# ProProject_ads1299_stm32f407__2024-07-30.net
KiCad netlist of a schematic drawn in EasyEDA Pro
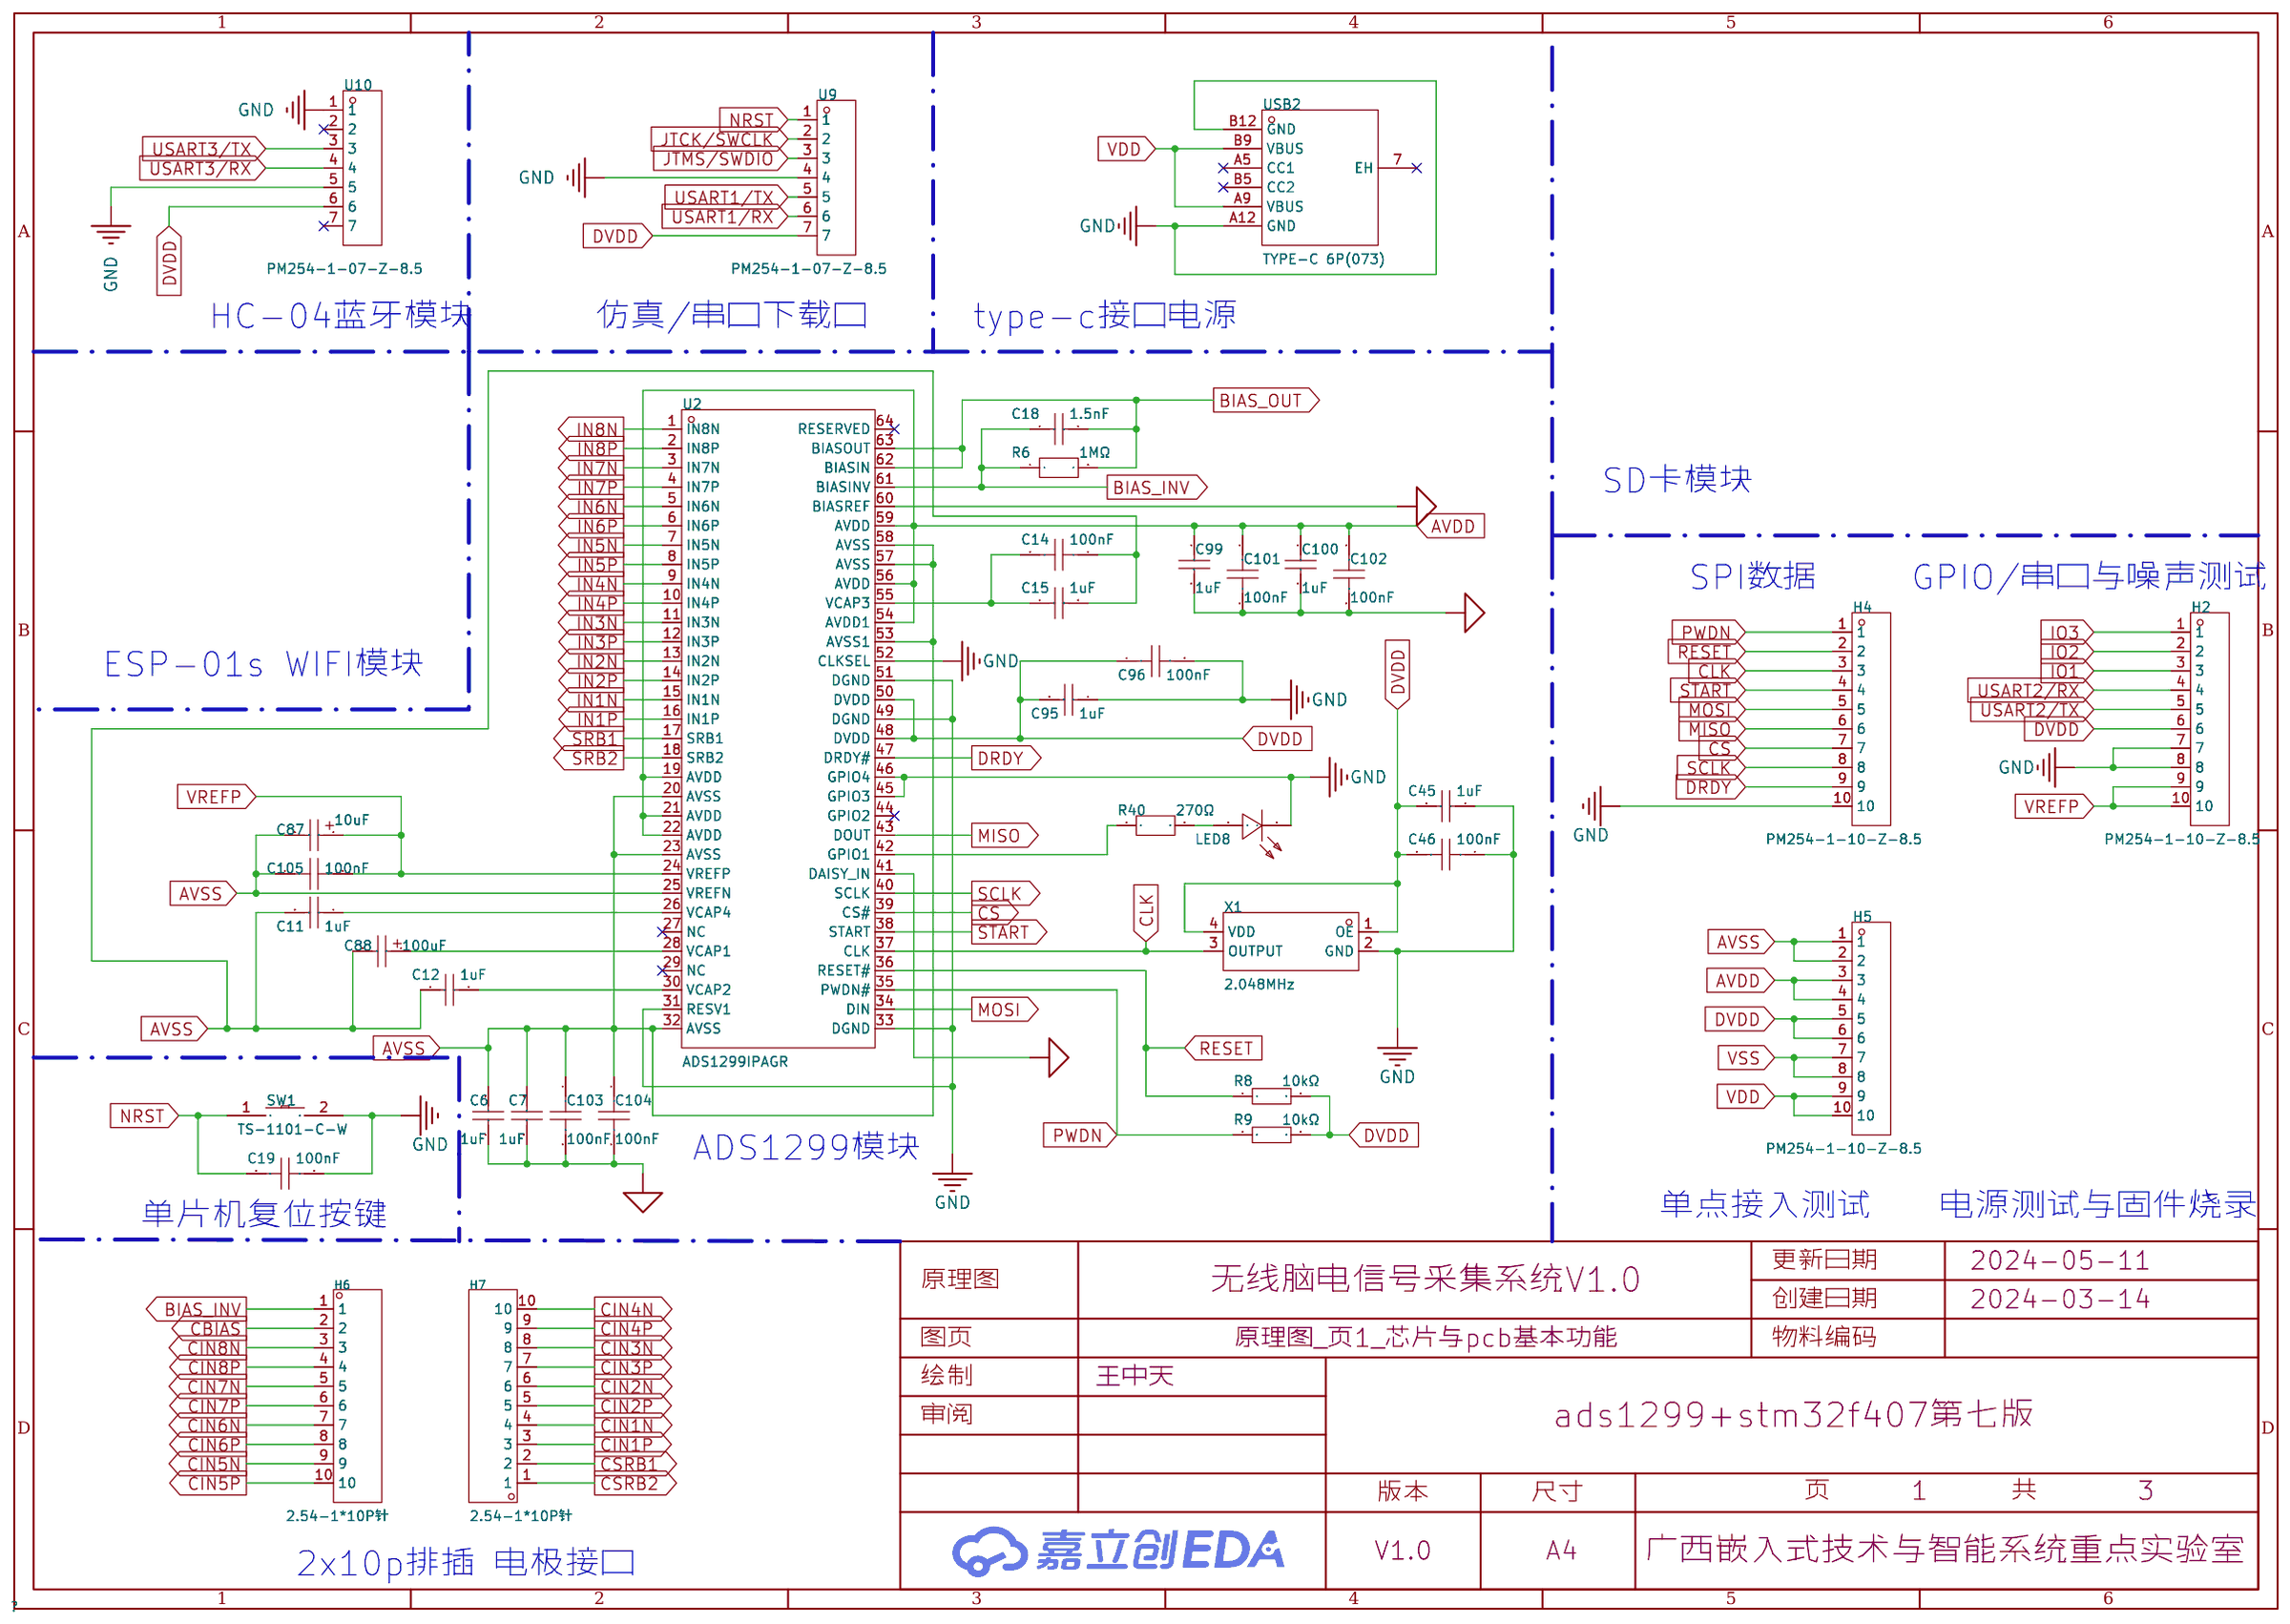
[diagram p0: 原理图_页1_芯片与pcb基本功能]
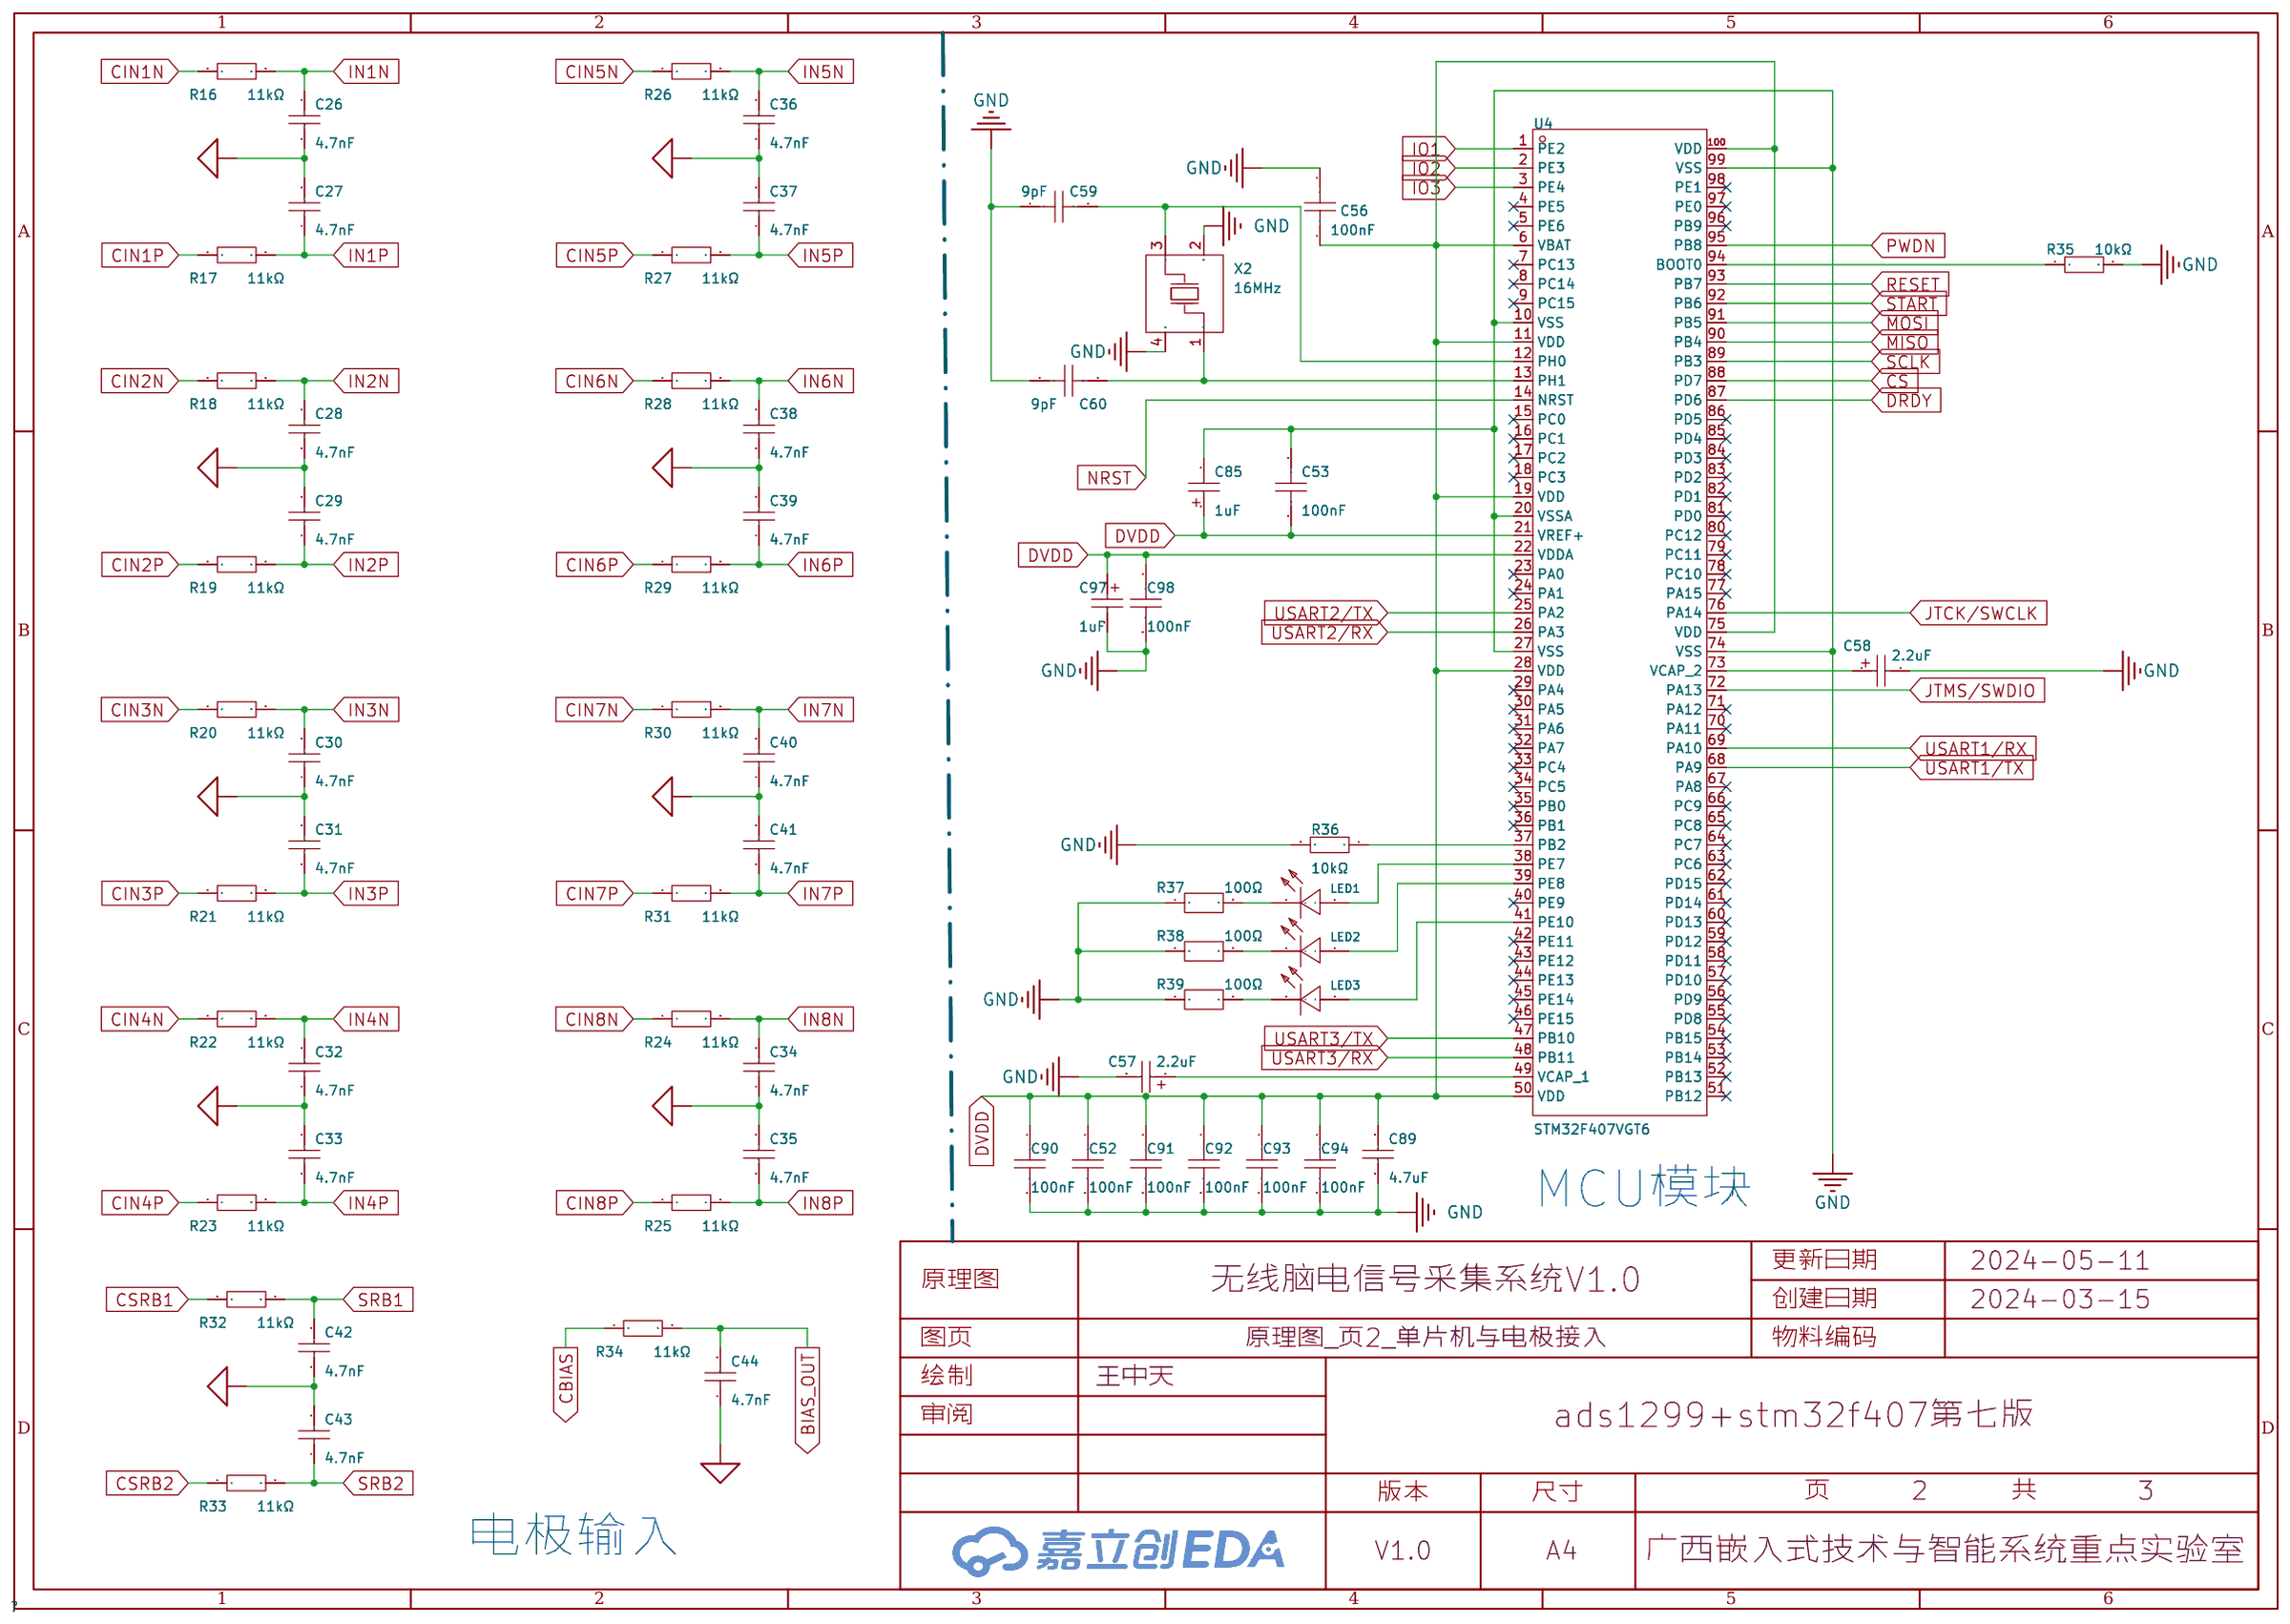
[diagram p1: 原理图_页2_单片机与电极接入]
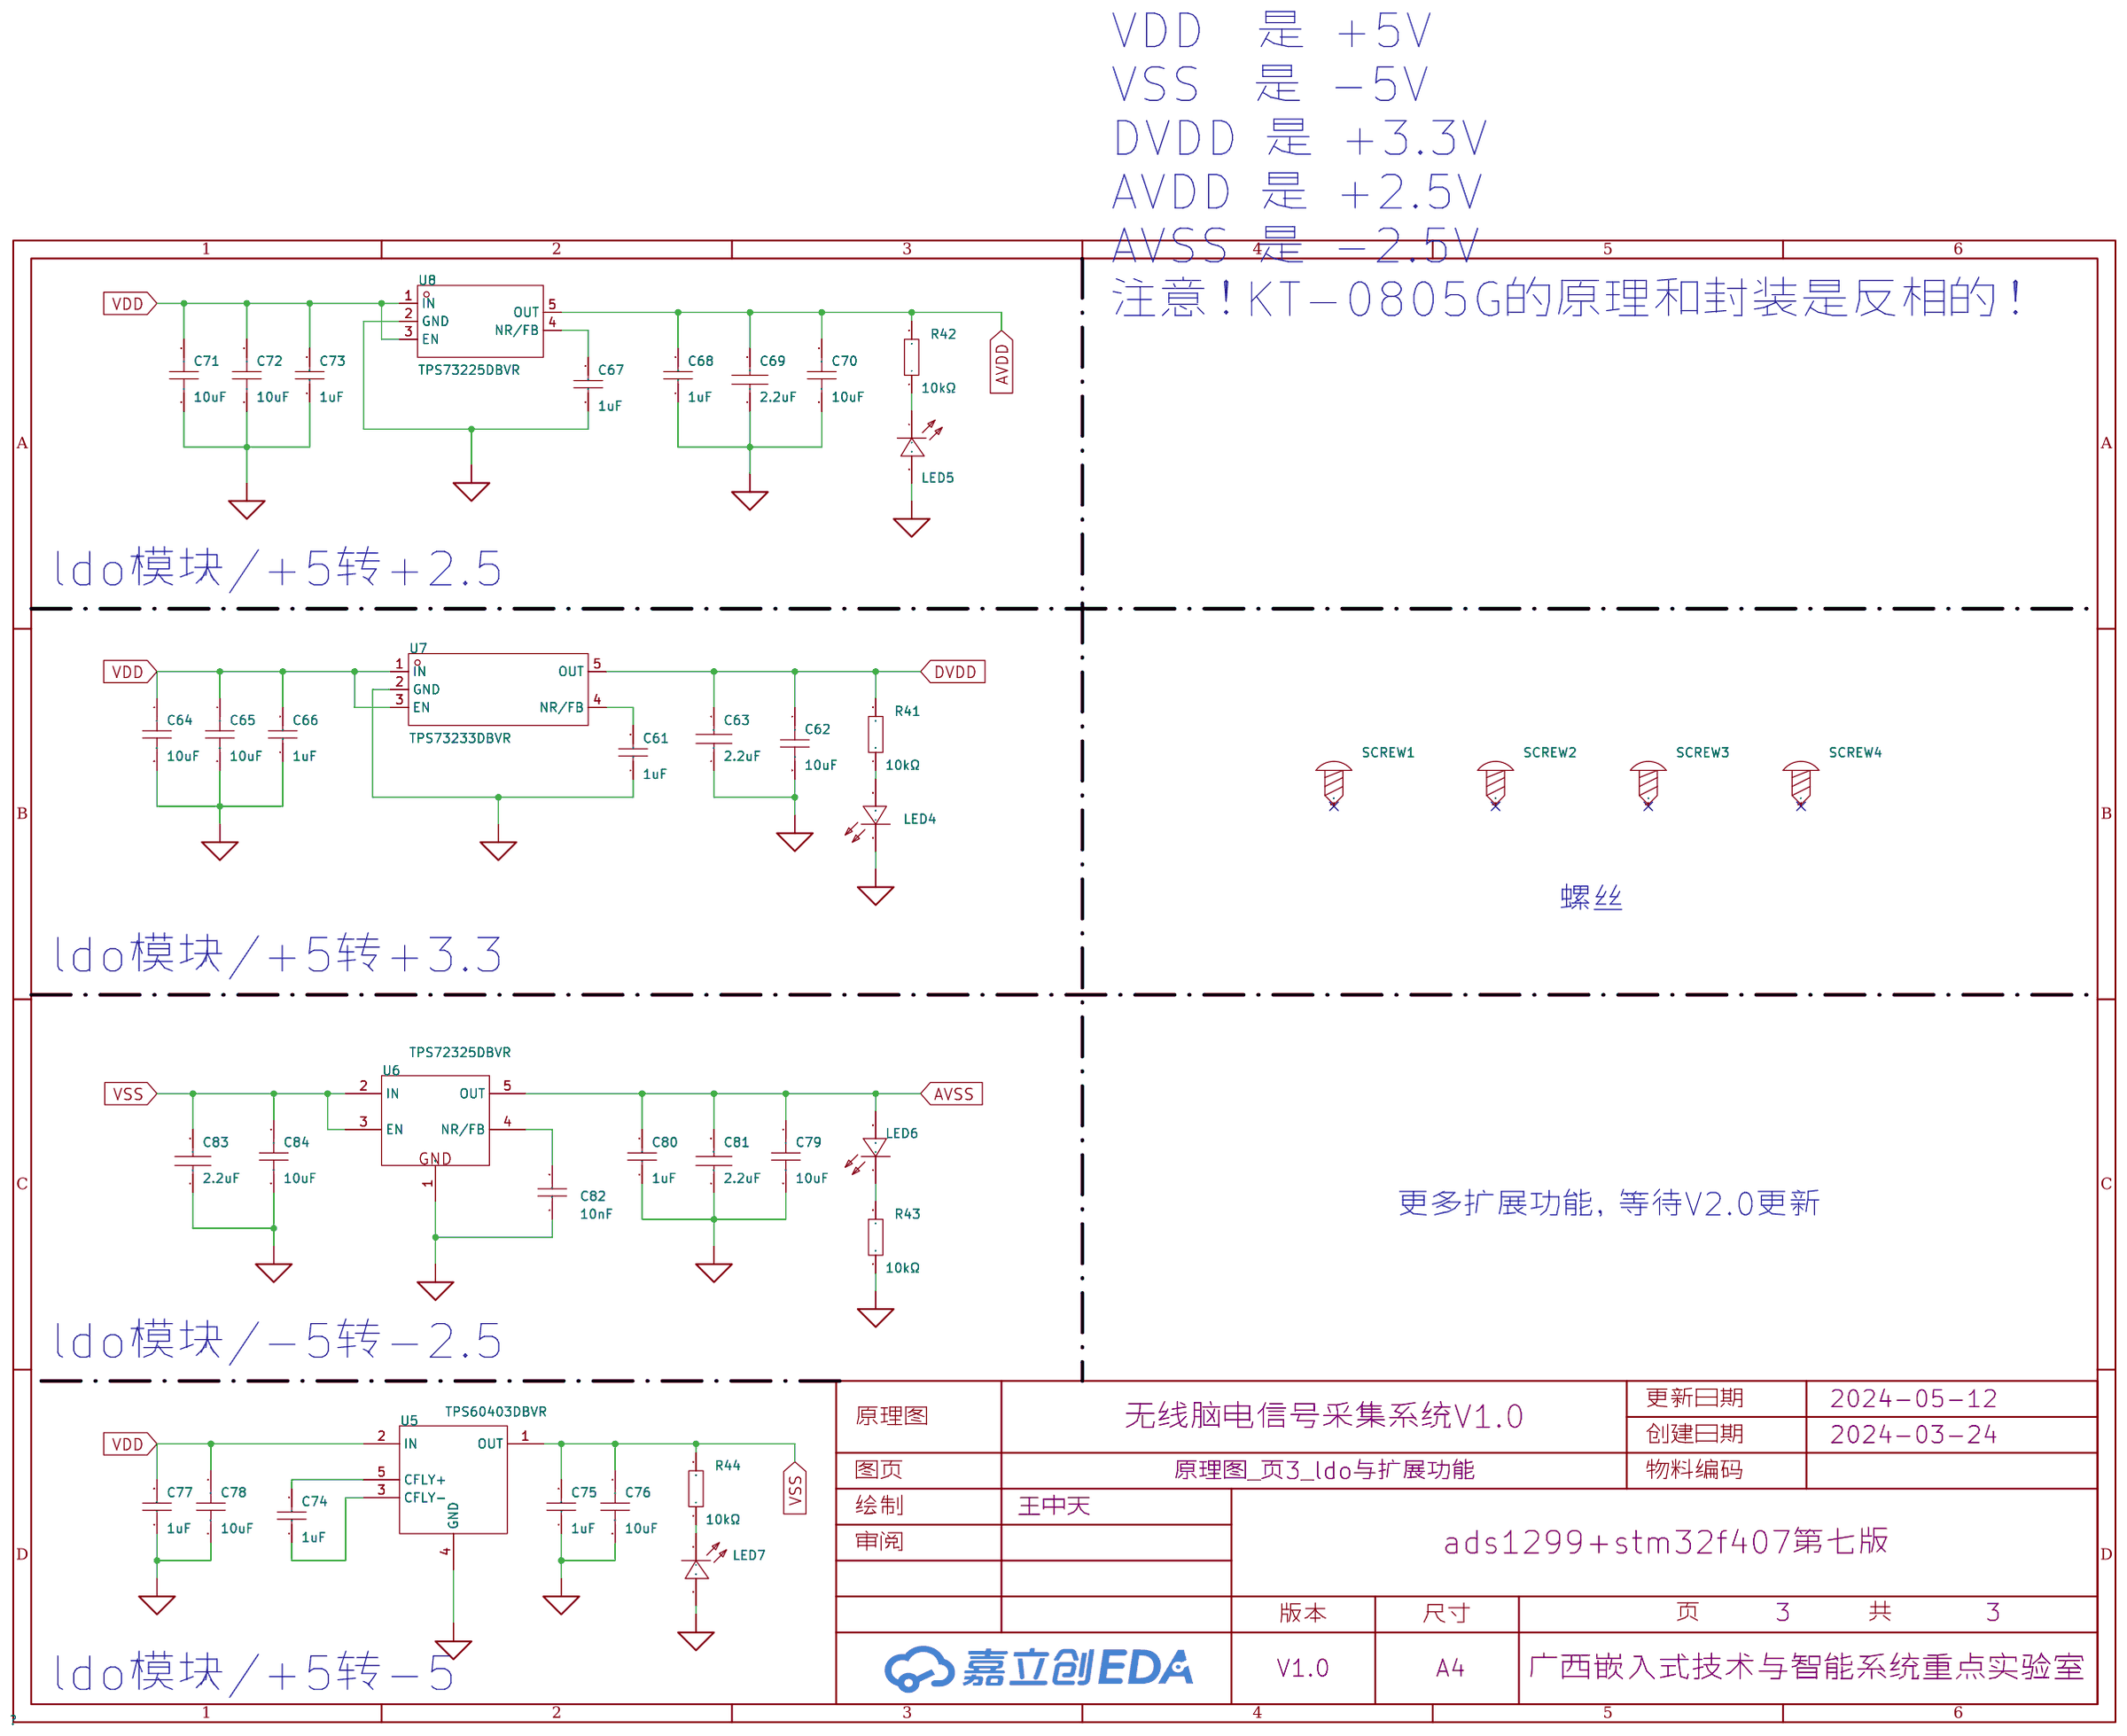
[diagram p2: 原理图_页3_ldo与扩展功能]

(export (version "E")
  (design (tool "Eeschema 10.0.6"))
  (components
    (comp (ref "C6")
      (value "1uF")
      (footprint "easyedapro:C0603")
      (description "容值:1uF;精度:±10%;额定电压:50V;材质(温度系数):X5R;")
      (fields
        (field (name "Manufacturer Part") "CL10A105KB8NNNC")
        (field (name "Manufacturer") "SAMSUNG(三星)")
      )
      (libsource (lib "easyedapro") (part "CL10A105KB8NNNC"))
    )
    (comp (ref "C7")
      (value "1uF")
      (footprint "easyedapro:C0603")
      (description "容值:1uF;精度:±10%;额定电压:50V;材质(温度系数):X5R;")
      (fields
        (field (name "Manufacturer Part") "CL10A105KB8NNNC")
        (field (name "Manufacturer") "SAMSUNG(三星)")
      )
      (libsource (lib "easyedapro") (part "CL10A105KB8NNNC"))
    )
    (comp (ref "C11")
      (value "1uF")
      (footprint "easyedapro:C0603")
      (description "容值:1uF;精度:±10%;额定电压:50V;材质(温度系数):X5R;")
      (fields
        (field (name "Manufacturer Part") "CL10A105KB8NNNC")
        (field (name "Manufacturer") "SAMSUNG(三星)")
      )
      (libsource (lib "easyedapro") (part "CL10A105KB8NNNC"))
    )
    (comp (ref "C12")
      (value "1uF")
      (footprint "easyedapro:C0603")
      (description "容值:1uF;精度:±10%;额定电压:50V;材质(温度系数):X5R;")
      (fields
        (field (name "Manufacturer Part") "CL10A105KB8NNNC")
        (field (name "Manufacturer") "SAMSUNG(三星)")
      )
      (libsource (lib "easyedapro") (part "CL10A105KB8NNNC"))
    )
    (comp (ref "C14")
      (value "100nF")
      (footprint "easyedapro:C0603")
      (description "容值:100nF;精度:±10%;额定电压:16V;材质(温度系数):X7R;")
      (fields
        (field (name "Manufacturer Part") "CC0603KRX7R9BB104")
        (field (name "Manufacturer") "YAGEO(国巨)")
      )
      (libsource (lib "easyedapro") (part "C0603C104K4RAC7867"))
    )
    (comp (ref "C15")
      (value "1uF")
      (footprint "easyedapro:C0603")
      (description "容值:1uF;精度:±10%;额定电压:50V;材质(温度系数):X5R;")
      (fields
        (field (name "Manufacturer Part") "CL10A105KB8NNNC")
        (field (name "Manufacturer") "SAMSUNG(三星)")
      )
      (libsource (lib "easyedapro") (part "CL10A105KB8NNNC"))
    )
    (comp (ref "C18")
      (value "1.5nF")
      (footprint "easyedapro:C0603")
      (description "容值:1.5nF;精度:±10%;额定电压:50V;材质(温度系数):X7R;")
      (fields (field (name "Manufacturer Part") "0603B152K500NT") (field (name "Manufacturer") "FH(风华)"))
      (libsource (lib "easyedapro") (part "0603B152K500NT"))
    )
    (comp (ref "C19")
      (value "100nF")
      (footprint "easyedapro:C0603")
      (description "容值:100nF;精度:±10%;额定电压:16V;材质(温度系数):X7R;")
      (fields
        (field (name "Manufacturer Part") "CC0603KRX7R9BB104")
        (field (name "Manufacturer") "YAGEO(国巨)")
      )
      (libsource (lib "easyedapro") (part "C0603C104K4RAC7867"))
    )
    (comp (ref "C45")
      (value "1uF")
      (footprint "easyedapro:C0603")
      (description "容值:1uF;精度:±10%;额定电压:50V;材质(温度系数):X5R;")
      (fields
        (field (name "Manufacturer Part") "CL10A105KB8NNNC")
        (field (name "Manufacturer") "SAMSUNG(三星)")
      )
      (libsource (lib "easyedapro") (part "CL10A105KB8NNNC"))
    )
    (comp (ref "C46")
      (value "100nF")
      (footprint "easyedapro:C0603")
      (description "容值:100nF;精度:±10%;额定电压:16V;材质(温度系数):X7R;")
      (fields
        (field (name "Manufacturer Part") "CC0603KRX7R9BB104")
        (field (name "Manufacturer") "YAGEO(国巨)")
      )
      (libsource (lib "easyedapro") (part "C0603C104K4RAC7867"))
    )
    (comp (ref "C87")
      (value "10uF")
      (footprint "easyedapro:CAP-SMD_L3.2-W1.6-RD-C7171")
      (description "容值:10uF;精度:±10%;额定电压:16V;等效串联电阻:3Ω@100kHz;")
      (fields
        (field (name "Manufacturer Part") "CL10A106KP8NNNC")
        (field (name "Manufacturer") "SAMSUNG(三星)")
      )
      (libsource (lib "easyedapro") (part "TAJA106K016RNJ"))
    )
    (comp (ref "C88")
      (value "100uF")
      (footprint "easyedapro:CASE-B_3528")
      (description "容值:100uF;精度:±10%;额定电压:6.3V;等效串联电阻:1.7Ω@100kHz;")
      (fields (field (name "Manufacturer Part") "TAJB107K006RNJ") (field (name "Manufacturer") "Kyocera AVX"))
      (libsource (lib "easyedapro") (part "TAJB107K006RNJ"))
    )
    (comp (ref "C95")
      (value "1uF")
      (footprint "easyedapro:C0603")
      (description "容值:1uF;精度:±10%;额定电压:50V;材质(温度系数):X5R;")
      (fields
        (field (name "Manufacturer Part") "CL10A105KB8NNNC")
        (field (name "Manufacturer") "SAMSUNG(三星)")
      )
      (libsource (lib "easyedapro") (part "CL10A105KB8NNNC"))
    )
    (comp (ref "C96")
      (value "100nF")
      (footprint "easyedapro:C0603")
      (description "容值:100nF;精度:±10%;额定电压:16V;材质(温度系数):X7R;")
      (fields
        (field (name "Manufacturer Part") "CC0603KRX7R9BB104")
        (field (name "Manufacturer") "YAGEO(国巨)")
      )
      (libsource (lib "easyedapro") (part "C0603C104K4RAC7867"))
    )
    (comp (ref "C99")
      (value "1uF")
      (footprint "easyedapro:C0603")
      (description "容值:1uF;精度:±10%;额定电压:50V;材质(温度系数):X5R;")
      (fields
        (field (name "Manufacturer Part") "CL10A105KB8NNNC")
        (field (name "Manufacturer") "SAMSUNG(三星)")
      )
      (libsource (lib "easyedapro") (part "CL10A105KB8NNNC"))
    )
    (comp (ref "C100")
      (value "1uF")
      (footprint "easyedapro:C0603")
      (description "容值:1uF;精度:±10%;额定电压:50V;材质(温度系数):X5R;")
      (fields
        (field (name "Manufacturer Part") "CL10A105KB8NNNC")
        (field (name "Manufacturer") "SAMSUNG(三星)")
      )
      (libsource (lib "easyedapro") (part "CL10A105KB8NNNC"))
    )
    (comp (ref "C101")
      (value "100nF")
      (footprint "easyedapro:C0603")
      (description "容值:100nF;精度:±10%;额定电压:16V;材质(温度系数):X7R;")
      (fields
        (field (name "Manufacturer Part") "CC0603KRX7R9BB104")
        (field (name "Manufacturer") "YAGEO(国巨)")
      )
      (libsource (lib "easyedapro") (part "C0603C104K4RAC7867"))
    )
    (comp (ref "C102")
      (value "100nF")
      (footprint "easyedapro:C0603")
      (description "容值:100nF;精度:±10%;额定电压:16V;材质(温度系数):X7R;")
      (fields
        (field (name "Manufacturer Part") "CC0603KRX7R9BB104")
        (field (name "Manufacturer") "YAGEO(国巨)")
      )
      (libsource (lib "easyedapro") (part "C0603C104K4RAC7867"))
    )
    (comp (ref "C103")
      (value "100nF")
      (footprint "easyedapro:C0603")
      (description "容值:100nF;精度:±10%;额定电压:16V;材质(温度系数):X7R;")
      (fields
        (field (name "Manufacturer Part") "CC0603KRX7R9BB104")
        (field (name "Manufacturer") "YAGEO(国巨)")
      )
      (libsource (lib "easyedapro") (part "C0603C104K4RAC7867"))
    )
    (comp (ref "C104")
      (value "100nF")
      (footprint "easyedapro:C0603")
      (description "容值:100nF;精度:±10%;额定电压:16V;材质(温度系数):X7R;")
      (fields
        (field (name "Manufacturer Part") "CC0603KRX7R9BB104")
        (field (name "Manufacturer") "YAGEO(国巨)")
      )
      (libsource (lib "easyedapro") (part "C0603C104K4RAC7867"))
    )
    (comp (ref "C105")
      (value "100nF")
      (footprint "easyedapro:C0603")
      (description "容值:100nF;精度:±10%;额定电压:16V;材质(温度系数):X7R;")
      (fields
        (field (name "Manufacturer Part") "CC0603KRX7R9BB104")
        (field (name "Manufacturer") "YAGEO(国巨)")
      )
      (libsource (lib "easyedapro") (part "C0603C104K4RAC7867"))
    )
    (comp (ref "H2")
      (value "PM254-1-10-Z-8.5")
      (footprint "easyedapro:HDR-TH_10P-P2.54-V-F")
      (fields (field (name "Manufacturer") "HCTL(华灿天禄)"))
      (libsource (lib "easyedapro") (part "PM254-1-10-Z-8.5"))
    )
    (comp (ref "H4")
      (value "PM254-1-10-Z-8.5")
      (footprint "easyedapro:HDR-TH_10P-P2.54-V-F")
      (fields (field (name "Manufacturer") "HCTL(华灿天禄)"))
      (libsource (lib "easyedapro") (part "PM254-1-10-Z-8.5"))
    )
    (comp (ref "H5")
      (value "PM254-1-10-Z-8.5")
      (footprint "easyedapro:HDR-TH_10P-P2.54-V-F")
      (fields (field (name "Manufacturer") "HCTL(华灿天禄)"))
      (libsource (lib "easyedapro") (part "PM254-1-10-Z-8.5"))
    )
    (comp (ref "H6")
      (value "2.54-1*10P针")
      (footprint "easyedapro:HDR-TH_10P-P2.54-V-M-1")
      (fields (field (name "Manufacturer") "BOOMELE(博穆精密)"))
      (libsource (lib "easyedapro") (part "Header-Male-2.54_1x10"))
    )
    (comp (ref "H7")
      (value "2.54-1*10P针")
      (footprint "easyedapro:HDR-TH_10P-P2.54-V-M-1")
      (fields (field (name "Manufacturer") "BOOMELE(博穆精密)"))
      (libsource (lib "easyedapro") (part "Header-Male-2.54_1x10"))
    )
    (comp (ref "LED8")
      (value "KT-0603W")
      (footprint "easyedapro:LED0603-R-RD_GREEN")
      (fields (field (name "Manufacturer") "KENTO"))
      (libsource (lib "easyedapro") (part "HL-PST-1608U51GC"))
    )
    (comp (ref "R6")
      (value "1MΩ")
      (footprint "easyedapro:R0805")
      (description "电阻类型:薄膜电阻;阻值:1MΩ;精度:±0.1%;功率:125mW;最大工作电压:100V;温度系数:±25ppm/°C;")
      (fields
        (field (name "Manufacturer Part") "0805W8F1004T5E")
        (field (name "Manufacturer") "UNI-ROYAL(厚声)")
      )
      (libsource (lib "easyedapro") (part "ERA6AEB105V"))
    )
    (comp (ref "R8")
      (value "10kΩ")
      (footprint "easyedapro:R0603")
      (description "电阻类型:厚膜电阻;阻值:10kΩ;精度:±1%;功率:100mW;最大工作电压:-;温度系数:±100ppm/°C;")
      (fields
        (field (name "Manufacturer Part") "0603WAF1002T5E")
        (field (name "Manufacturer") "UNI-ROYAL(厚声)")
      )
      (libsource (lib "easyedapro") (part "ERJ-3EKF1002V"))
    )
    (comp (ref "R9")
      (value "10kΩ")
      (footprint "easyedapro:R0603")
      (description "电阻类型:厚膜电阻;阻值:10kΩ;精度:±1%;功率:100mW;最大工作电压:-;温度系数:±100ppm/°C;")
      (fields
        (field (name "Manufacturer Part") "0603WAF1002T5E")
        (field (name "Manufacturer") "UNI-ROYAL(厚声)")
      )
      (libsource (lib "easyedapro") (part "ERJ-3EKF1002V"))
    )
    (comp (ref "R40")
      (value "270Ω")
      (footprint "easyedapro:R0603")
      (description "电阻类型:厚膜电阻;阻值:270Ω;精度:±1%;功率:100mW;最大工作电压:-;温度系数:±100ppm/°C;")
      (fields
        (field (name "Manufacturer Part") "0603WAF2700T5E")
        (field (name "Manufacturer") "UNI-ROYAL(厚声)")
      )
      (libsource (lib "easyedapro") (part "ERJ3EKF2700V"))
    )
    (comp (ref "SW1")
      (value "TS-1101-C-W")
      (footprint "easyedapro:SW-SMD_L6.0-W3.3-LS8.0")
      (fields (field (name "Manufacturer") "XKB Connectivity(中国星坤)"))
      (libsource (lib "easyedapro") (part "TS-1101-C-W"))
    )
    (comp (ref "U2")
      (value "ADS1299IPAGR")
      (footprint "easyedapro:TQFP-64_L10.0-W10.0-P0.50-LS12.0-TL")
      (description "电源电压:5V；1.8V~3.6V;")
      (fields (field (name "Manufacturer") "TI(德州仪器)"))
      (libsource (lib "easyedapro") (part "ADS1299IPAGR"))
    )
    (comp (ref "U9")
      (value "PM254-1-07-Z-8.5")
      (footprint "easyedapro:HDR-TH_7P-P2.54-V-F")
      (fields (field (name "Manufacturer") "HCTL(华灿天禄)"))
      (libsource (lib "easyedapro") (part "PM254-1-07-Z-8.5"))
    )
    (comp (ref "U10")
      (value "PM254-1-07-Z-8.5")
      (footprint "easyedapro:HDR-TH_7P-P2.54-V-F")
      (fields (field (name "Manufacturer") "HCTL(华灿天禄)"))
      (libsource (lib "easyedapro") (part "PM254-1-07-Z-8.5"))
    )
    (comp (ref "USB2")
      (value "TYPE-C 6P(073)")
      (footprint "easyedapro:TYPE-C-SMD_TYPE-C-6P")
      (description "连接器类型:Type-C;标准:-;公母:母;端口数量:1;触点数量:6P;安装方式:卧贴;额定电流 - 电源:5A;工作温度范围:-25°C~+85°C;")
      (fields (field (name "Manufacturer") "SHOU HAN(首韩)"))
      (libsource (lib "easyedapro") (part "TYPE-C 6P(073)"))
    )
    (comp (ref "X1")
      (value "2.048MHz")
      (footprint "easyedapro:OSC-SMD_4P-L7.0-W5.0-BL")
      (description "频率:2.048MHz;输出模式:CMOS;工作电压:3.3V;供电电流:10mA;频率稳定度(全温):±30ppm;")
      (fields
        (field (name "Manufacturer Part") "S7D2.048000B20F30T")
        (field (name "Manufacturer") "SCTF(星通时频)")
      )
      (libsource (lib "easyedapro") (part "S7D2.048000B20F30T"))
    )
    (comp (ref "C26")
      (value "4.7nF")
      (footprint "easyedapro:C0603")
      (description "容值:4.7nF;精度:±10%;额定电压:50V;材质(温度系数):X7R;")
      (fields (field (name "Manufacturer Part") "0603B472K500NT") (field (name "Manufacturer") "FH(风华)"))
      (libsource (lib "easyedapro") (part "0603B472K500NT"))
    )
    (comp (ref "C27")
      (value "4.7nF")
      (footprint "easyedapro:C0603")
      (description "容值:4.7nF;精度:±10%;额定电压:50V;材质(温度系数):X7R;")
      (fields (field (name "Manufacturer Part") "0603B472K500NT") (field (name "Manufacturer") "FH(风华)"))
      (libsource (lib "easyedapro") (part "0603B472K500NT"))
    )
    (comp (ref "C28")
      (value "4.7nF")
      (footprint "easyedapro:C0603")
      (description "容值:4.7nF;精度:±10%;额定电压:50V;材质(温度系数):X7R;")
      (fields (field (name "Manufacturer Part") "0603B472K500NT") (field (name "Manufacturer") "FH(风华)"))
      (libsource (lib "easyedapro") (part "0603B472K500NT"))
    )
    (comp (ref "C29")
      (value "4.7nF")
      (footprint "easyedapro:C0603")
      (description "容值:4.7nF;精度:±10%;额定电压:50V;材质(温度系数):X7R;")
      (fields (field (name "Manufacturer Part") "0603B472K500NT") (field (name "Manufacturer") "FH(风华)"))
      (libsource (lib "easyedapro") (part "0603B472K500NT"))
    )
    (comp (ref "C30")
      (value "4.7nF")
      (footprint "easyedapro:C0603")
      (description "容值:4.7nF;精度:±10%;额定电压:50V;材质(温度系数):X7R;")
      (fields (field (name "Manufacturer Part") "0603B472K500NT") (field (name "Manufacturer") "FH(风华)"))
      (libsource (lib "easyedapro") (part "0603B472K500NT"))
    )
    (comp (ref "C31")
      (value "4.7nF")
      (footprint "easyedapro:C0603")
      (description "容值:4.7nF;精度:±10%;额定电压:50V;材质(温度系数):X7R;")
      (fields (field (name "Manufacturer Part") "0603B472K500NT") (field (name "Manufacturer") "FH(风华)"))
      (libsource (lib "easyedapro") (part "0603B472K500NT"))
    )
    (comp (ref "C32")
      (value "4.7nF")
      (footprint "easyedapro:C0603")
      (description "容值:4.7nF;精度:±10%;额定电压:50V;材质(温度系数):X7R;")
      (fields (field (name "Manufacturer Part") "0603B472K500NT") (field (name "Manufacturer") "FH(风华)"))
      (libsource (lib "easyedapro") (part "0603B472K500NT"))
    )
    (comp (ref "C33")
      (value "4.7nF")
      (footprint "easyedapro:C0603")
      (description "容值:4.7nF;精度:±10%;额定电压:50V;材质(温度系数):X7R;")
      (fields (field (name "Manufacturer Part") "0603B472K500NT") (field (name "Manufacturer") "FH(风华)"))
      (libsource (lib "easyedapro") (part "0603B472K500NT"))
    )
    (comp (ref "C34")
      (value "4.7nF")
      (footprint "easyedapro:C0603")
      (description "容值:4.7nF;精度:±10%;额定电压:50V;材质(温度系数):X7R;")
      (fields (field (name "Manufacturer Part") "0603B472K500NT") (field (name "Manufacturer") "FH(风华)"))
      (libsource (lib "easyedapro") (part "0603B472K500NT"))
    )
    (comp (ref "C35")
      (value "4.7nF")
      (footprint "easyedapro:C0603")
      (description "容值:4.7nF;精度:±10%;额定电压:50V;材质(温度系数):X7R;")
      (fields (field (name "Manufacturer Part") "0603B472K500NT") (field (name "Manufacturer") "FH(风华)"))
      (libsource (lib "easyedapro") (part "0603B472K500NT"))
    )
    (comp (ref "C36")
      (value "4.7nF")
      (footprint "easyedapro:C0603")
      (description "容值:4.7nF;精度:±10%;额定电压:50V;材质(温度系数):X7R;")
      (fields (field (name "Manufacturer Part") "0603B472K500NT") (field (name "Manufacturer") "FH(风华)"))
      (libsource (lib "easyedapro") (part "0603B472K500NT"))
    )
    (comp (ref "C37")
      (value "4.7nF")
      (footprint "easyedapro:C0603")
      (description "容值:4.7nF;精度:±10%;额定电压:50V;材质(温度系数):X7R;")
      (fields (field (name "Manufacturer Part") "0603B472K500NT") (field (name "Manufacturer") "FH(风华)"))
      (libsource (lib "easyedapro") (part "0603B472K500NT"))
    )
    (comp (ref "C38")
      (value "4.7nF")
      (footprint "easyedapro:C0603")
      (description "容值:4.7nF;精度:±10%;额定电压:50V;材质(温度系数):X7R;")
      (fields (field (name "Manufacturer Part") "0603B472K500NT") (field (name "Manufacturer") "FH(风华)"))
      (libsource (lib "easyedapro") (part "0603B472K500NT"))
    )
    (comp (ref "C39")
      (value "4.7nF")
      (footprint "easyedapro:C0603")
      (description "容值:4.7nF;精度:±10%;额定电压:50V;材质(温度系数):X7R;")
      (fields (field (name "Manufacturer Part") "0603B472K500NT") (field (name "Manufacturer") "FH(风华)"))
      (libsource (lib "easyedapro") (part "0603B472K500NT"))
    )
    (comp (ref "C40")
      (value "4.7nF")
      (footprint "easyedapro:C0603")
      (description "容值:4.7nF;精度:±10%;额定电压:50V;材质(温度系数):X7R;")
      (fields (field (name "Manufacturer Part") "0603B472K500NT") (field (name "Manufacturer") "FH(风华)"))
      (libsource (lib "easyedapro") (part "0603B472K500NT"))
    )
    (comp (ref "C41")
      (value "4.7nF")
      (footprint "easyedapro:C0603")
      (description "容值:4.7nF;精度:±10%;额定电压:50V;材质(温度系数):X7R;")
      (fields (field (name "Manufacturer Part") "0603B472K500NT") (field (name "Manufacturer") "FH(风华)"))
      (libsource (lib "easyedapro") (part "0603B472K500NT"))
    )
    (comp (ref "C42")
      (value "4.7nF")
      (footprint "easyedapro:C0603")
      (description "容值:4.7nF;精度:±10%;额定电压:50V;材质(温度系数):X7R;")
      (fields (field (name "Manufacturer Part") "0603B472K500NT") (field (name "Manufacturer") "FH(风华)"))
      (libsource (lib "easyedapro") (part "0603B472K500NT"))
    )
    (comp (ref "C43")
      (value "4.7nF")
      (footprint "easyedapro:C0603")
      (description "容值:4.7nF;精度:±10%;额定电压:50V;材质(温度系数):X7R;")
      (fields (field (name "Manufacturer Part") "0603B472K500NT") (field (name "Manufacturer") "FH(风华)"))
      (libsource (lib "easyedapro") (part "0603B472K500NT"))
    )
    (comp (ref "C44")
      (value "4.7nF")
      (footprint "easyedapro:C0603")
      (description "容值:4.7nF;精度:±10%;额定电压:50V;材质(温度系数):X7R;")
      (fields (field (name "Manufacturer Part") "0603B472K500NT") (field (name "Manufacturer") "FH(风华)"))
      (libsource (lib "easyedapro") (part "0603B472K500NT"))
    )
    (comp (ref "C52")
      (value "100nF")
      (footprint "easyedapro:C0603")
      (description "容值:100nF;精度:±10%;额定电压:16V;材质(温度系数):X7R;")
      (fields
        (field (name "Manufacturer Part") "CC0603KRX7R9BB104")
        (field (name "Manufacturer") "YAGEO(国巨)")
      )
      (libsource (lib "easyedapro") (part "C0603C104K4RAC7867"))
    )
    (comp (ref "C53")
      (value "100nF")
      (footprint "easyedapro:C0603")
      (description "容值:100nF;精度:±10%;额定电压:16V;材质(温度系数):X7R;")
      (fields
        (field (name "Manufacturer Part") "CC0603KRX7R9BB104")
        (field (name "Manufacturer") "YAGEO(国巨)")
      )
      (libsource (lib "easyedapro") (part "C0603C104K4RAC7867"))
    )
    (comp (ref "C56")
      (value "100nF")
      (footprint "easyedapro:C0603")
      (description "容值:100nF;精度:±10%;额定电压:16V;材质(温度系数):X7R;")
      (fields
        (field (name "Manufacturer Part") "CC0603KRX7R9BB104")
        (field (name "Manufacturer") "YAGEO(国巨)")
      )
      (libsource (lib "easyedapro") (part "C0603C104K4RAC7867"))
    )
    (comp (ref "C57")
      (value "2.2uF")
      (footprint "easyedapro:CASE-A_3216")
      (description "容值:2.2uF;精度:±10%;额定电压:16V;等效串联电阻:6.5Ω@100kHz;")
      (fields
        (field (name "Manufacturer Part") "CL21A225KBQNNNE")
        (field (name "Manufacturer") "SAMSUNG(三星)")
      )
      (libsource (lib "easyedapro") (part "TAJA225K016RNJ"))
    )
    (comp (ref "C58")
      (value "2.2uF")
      (footprint "easyedapro:CASE-A_3216")
      (description "容值:2.2uF;精度:±10%;额定电压:16V;等效串联电阻:6.5Ω@100kHz;")
      (fields
        (field (name "Manufacturer Part") "CL21A225KBQNNNE")
        (field (name "Manufacturer") "SAMSUNG(三星)")
      )
      (libsource (lib "easyedapro") (part "TAJA225K016RNJ"))
    )
    (comp (ref "C59")
      (value "9pF")
      (footprint "easyedapro:C0402")
      (description "容值:9pF;额定电压:50V;材质(温度系数):C0G;")
      (fields
        (field (name "Manufacturer Part") "TCC0402COG9R0D500AT")
        (field (name "Manufacturer") "CCTC(三环)")
      )
      (libsource (lib "easyedapro") (part "TCC0402COG9R0D500AT"))
    )
    (comp (ref "C60")
      (value "9pF")
      (footprint "easyedapro:C0402")
      (description "容值:9pF;额定电压:50V;材质(温度系数):C0G;")
      (fields
        (field (name "Manufacturer Part") "TCC0402COG9R0D500AT")
        (field (name "Manufacturer") "CCTC(三环)")
      )
      (libsource (lib "easyedapro") (part "TCC0402COG9R0D500AT"))
    )
    (comp (ref "C85")
      (value "1uF")
      (footprint "easyedapro:CASE-A_3216")
      (description "容值:1uF;精度:±10%;额定电压:16V;等效串联电阻:11Ω;")
      (fields (field (name "Manufacturer Part") "TAJA105K016RNJ") (field (name "Manufacturer") "Kyocera AVX"))
      (libsource (lib "easyedapro") (part "TAJA105K016RNJ"))
    )
    (comp (ref "C89")
      (value "4.7uF")
      (footprint "easyedapro:C0603")
      (description "容值:4.7uF;精度:±10%;额定电压:16V;材质(温度系数):X5R;")
      (fields
        (field (name "Manufacturer Part") "CL10A475KO8NNNC")
        (field (name "Manufacturer") "SAMSUNG(三星)")
      )
      (libsource (lib "easyedapro") (part "CL10A475KO8NNNC"))
    )
    (comp (ref "C90")
      (value "100nF")
      (footprint "easyedapro:C0603")
      (description "容值:100nF;精度:±10%;额定电压:16V;材质(温度系数):X7R;")
      (fields
        (field (name "Manufacturer Part") "CC0603KRX7R9BB104")
        (field (name "Manufacturer") "YAGEO(国巨)")
      )
      (libsource (lib "easyedapro") (part "C0603C104K4RAC7867"))
    )
    (comp (ref "C91")
      (value "100nF")
      (footprint "easyedapro:C0603")
      (description "容值:100nF;精度:±10%;额定电压:16V;材质(温度系数):X7R;")
      (fields
        (field (name "Manufacturer Part") "CC0603KRX7R9BB104")
        (field (name "Manufacturer") "YAGEO(国巨)")
      )
      (libsource (lib "easyedapro") (part "C0603C104K4RAC7867"))
    )
    (comp (ref "C92")
      (value "100nF")
      (footprint "easyedapro:C0603")
      (description "容值:100nF;精度:±10%;额定电压:16V;材质(温度系数):X7R;")
      (fields
        (field (name "Manufacturer Part") "CC0603KRX7R9BB104")
        (field (name "Manufacturer") "YAGEO(国巨)")
      )
      (libsource (lib "easyedapro") (part "C0603C104K4RAC7867"))
    )
    (comp (ref "C93")
      (value "100nF")
      (footprint "easyedapro:C0603")
      (description "容值:100nF;精度:±10%;额定电压:16V;材质(温度系数):X7R;")
      (fields
        (field (name "Manufacturer Part") "CC0603KRX7R9BB104")
        (field (name "Manufacturer") "YAGEO(国巨)")
      )
      (libsource (lib "easyedapro") (part "C0603C104K4RAC7867"))
    )
    (comp (ref "C94")
      (value "100nF")
      (footprint "easyedapro:C0603")
      (description "容值:100nF;精度:±10%;额定电压:16V;材质(温度系数):X7R;")
      (fields
        (field (name "Manufacturer Part") "CC0603KRX7R9BB104")
        (field (name "Manufacturer") "YAGEO(国巨)")
      )
      (libsource (lib "easyedapro") (part "C0603C104K4RAC7867"))
    )
    (comp (ref "C97")
      (value "1uF")
      (footprint "easyedapro:CASE-A_3216")
      (description "容值:1uF;精度:±10%;额定电压:16V;等效串联电阻:11Ω;")
      (fields (field (name "Manufacturer Part") "TAJA105K016RNJ") (field (name "Manufacturer") "Kyocera AVX"))
      (libsource (lib "easyedapro") (part "TAJA105K016RNJ"))
    )
    (comp (ref "C98")
      (value "100nF")
      (footprint "easyedapro:C0603")
      (description "容值:100nF;精度:±10%;额定电压:16V;材质(温度系数):X7R;")
      (fields
        (field (name "Manufacturer Part") "CC0603KRX7R9BB104")
        (field (name "Manufacturer") "YAGEO(国巨)")
      )
      (libsource (lib "easyedapro") (part "C0603C104K4RAC7867"))
    )
    (comp (ref "LED1")
      (value "KT-0603R")
      (footprint "easyedapro:LED0603-RD")
      (fields (field (name "Manufacturer") "KENTO"))
      (libsource (lib "easyedapro") (part "LTST-C193KGKT-5A"))
    )
    (comp (ref "LED2")
      (value "KT-0603R")
      (footprint "easyedapro:LED0603-RD")
      (fields (field (name "Manufacturer") "KENTO"))
      (libsource (lib "easyedapro") (part "LTST-C193KGKT-5A"))
    )
    (comp (ref "LED3")
      (value "KT-0603R")
      (footprint "easyedapro:LED0603-RD")
      (fields (field (name "Manufacturer") "KENTO"))
      (libsource (lib "easyedapro") (part "LTST-C193KGKT-5A"))
    )
    (comp (ref "R16")
      (value "11kΩ")
      (footprint "easyedapro:R0402")
      (description "电阻类型:厚膜电阻;阻值:11kΩ;精度:±1%;功率:62.5mW;最大工作电压:50V;温度系数:±100ppm/°C;")
      (fields
        (field (name "Manufacturer Part") "0603WAF1102T5E")
        (field (name "Manufacturer") "UNI-ROYAL(厚声)")
      )
      (libsource (lib "easyedapro") (part "0402WGF1102TCE"))
    )
    (comp (ref "R17")
      (value "11kΩ")
      (footprint "easyedapro:R0402")
      (description "电阻类型:厚膜电阻;阻值:11kΩ;精度:±1%;功率:62.5mW;最大工作电压:50V;温度系数:±100ppm/°C;")
      (fields
        (field (name "Manufacturer Part") "0603WAF1102T5E")
        (field (name "Manufacturer") "UNI-ROYAL(厚声)")
      )
      (libsource (lib "easyedapro") (part "0402WGF1102TCE"))
    )
    (comp (ref "R18")
      (value "11kΩ")
      (footprint "easyedapro:R0402")
      (description "电阻类型:厚膜电阻;阻值:11kΩ;精度:±1%;功率:62.5mW;最大工作电压:50V;温度系数:±100ppm/°C;")
      (fields
        (field (name "Manufacturer Part") "0603WAF1102T5E")
        (field (name "Manufacturer") "UNI-ROYAL(厚声)")
      )
      (libsource (lib "easyedapro") (part "0402WGF1102TCE"))
    )
    (comp (ref "R19")
      (value "11kΩ")
      (footprint "easyedapro:R0402")
      (description "电阻类型:厚膜电阻;阻值:11kΩ;精度:±1%;功率:62.5mW;最大工作电压:50V;温度系数:±100ppm/°C;")
      (fields
        (field (name "Manufacturer Part") "0603WAF1102T5E")
        (field (name "Manufacturer") "UNI-ROYAL(厚声)")
      )
      (libsource (lib "easyedapro") (part "0402WGF1102TCE"))
    )
    (comp (ref "R20")
      (value "11kΩ")
      (footprint "easyedapro:R0402")
      (description "电阻类型:厚膜电阻;阻值:11kΩ;精度:±1%;功率:62.5mW;最大工作电压:50V;温度系数:±100ppm/°C;")
      (fields
        (field (name "Manufacturer Part") "0603WAF1102T5E")
        (field (name "Manufacturer") "UNI-ROYAL(厚声)")
      )
      (libsource (lib "easyedapro") (part "0402WGF1102TCE"))
    )
    (comp (ref "R21")
      (value "11kΩ")
      (footprint "easyedapro:R0402")
      (description "电阻类型:厚膜电阻;阻值:11kΩ;精度:±1%;功率:62.5mW;最大工作电压:50V;温度系数:±100ppm/°C;")
      (fields
        (field (name "Manufacturer Part") "0603WAF1102T5E")
        (field (name "Manufacturer") "UNI-ROYAL(厚声)")
      )
      (libsource (lib "easyedapro") (part "0402WGF1102TCE"))
    )
    (comp (ref "R22")
      (value "11kΩ")
      (footprint "easyedapro:R0402")
      (description "电阻类型:厚膜电阻;阻值:11kΩ;精度:±1%;功率:62.5mW;最大工作电压:50V;温度系数:±100ppm/°C;")
      (fields
        (field (name "Manufacturer Part") "0603WAF1102T5E")
        (field (name "Manufacturer") "UNI-ROYAL(厚声)")
      )
      (libsource (lib "easyedapro") (part "0402WGF1102TCE"))
    )
    (comp (ref "R23")
      (value "11kΩ")
      (footprint "easyedapro:R0402")
      (description "电阻类型:厚膜电阻;阻值:11kΩ;精度:±1%;功率:62.5mW;最大工作电压:50V;温度系数:±100ppm/°C;")
      (fields
        (field (name "Manufacturer Part") "0603WAF1102T5E")
        (field (name "Manufacturer") "UNI-ROYAL(厚声)")
      )
      (libsource (lib "easyedapro") (part "0402WGF1102TCE"))
    )
    (comp (ref "R24")
      (value "11kΩ")
      (footprint "easyedapro:R0402")
      (description "电阻类型:厚膜电阻;阻值:11kΩ;精度:±1%;功率:62.5mW;最大工作电压:50V;温度系数:±100ppm/°C;")
      (fields
        (field (name "Manufacturer Part") "0603WAF1102T5E")
        (field (name "Manufacturer") "UNI-ROYAL(厚声)")
      )
      (libsource (lib "easyedapro") (part "0402WGF1102TCE"))
    )
    (comp (ref "R25")
      (value "11kΩ")
      (footprint "easyedapro:R0402")
      (description "电阻类型:厚膜电阻;阻值:11kΩ;精度:±1%;功率:62.5mW;最大工作电压:50V;温度系数:±100ppm/°C;")
      (fields
        (field (name "Manufacturer Part") "0603WAF1102T5E")
        (field (name "Manufacturer") "UNI-ROYAL(厚声)")
      )
      (libsource (lib "easyedapro") (part "0402WGF1102TCE"))
    )
    (comp (ref "R26")
      (value "11kΩ")
      (footprint "easyedapro:R0402")
      (description "电阻类型:厚膜电阻;阻值:11kΩ;精度:±1%;功率:62.5mW;最大工作电压:50V;温度系数:±100ppm/°C;")
      (fields
        (field (name "Manufacturer Part") "0603WAF1102T5E")
        (field (name "Manufacturer") "UNI-ROYAL(厚声)")
      )
      (libsource (lib "easyedapro") (part "0402WGF1102TCE"))
    )
    (comp (ref "R27")
      (value "11kΩ")
      (footprint "easyedapro:R0402")
      (description "电阻类型:厚膜电阻;阻值:11kΩ;精度:±1%;功率:62.5mW;最大工作电压:50V;温度系数:±100ppm/°C;")
      (fields
        (field (name "Manufacturer Part") "0603WAF1102T5E")
        (field (name "Manufacturer") "UNI-ROYAL(厚声)")
      )
      (libsource (lib "easyedapro") (part "0402WGF1102TCE"))
    )
    (comp (ref "R28")
      (value "11kΩ")
      (footprint "easyedapro:R0402")
      (description "电阻类型:厚膜电阻;阻值:11kΩ;精度:±1%;功率:62.5mW;最大工作电压:50V;温度系数:±100ppm/°C;")
      (fields
        (field (name "Manufacturer Part") "0603WAF1102T5E")
        (field (name "Manufacturer") "UNI-ROYAL(厚声)")
      )
      (libsource (lib "easyedapro") (part "0402WGF1102TCE"))
    )
    (comp (ref "R29")
      (value "11kΩ")
      (footprint "easyedapro:R0402")
      (description "电阻类型:厚膜电阻;阻值:11kΩ;精度:±1%;功率:62.5mW;最大工作电压:50V;温度系数:±100ppm/°C;")
      (fields
        (field (name "Manufacturer Part") "0603WAF1102T5E")
        (field (name "Manufacturer") "UNI-ROYAL(厚声)")
      )
      (libsource (lib "easyedapro") (part "0402WGF1102TCE"))
    )
    (comp (ref "R30")
      (value "11kΩ")
      (footprint "easyedapro:R0402")
      (description "电阻类型:厚膜电阻;阻值:11kΩ;精度:±1%;功率:62.5mW;最大工作电压:50V;温度系数:±100ppm/°C;")
      (fields
        (field (name "Manufacturer Part") "0603WAF1102T5E")
        (field (name "Manufacturer") "UNI-ROYAL(厚声)")
      )
      (libsource (lib "easyedapro") (part "0402WGF1102TCE"))
    )
    (comp (ref "R31")
      (value "11kΩ")
      (footprint "easyedapro:R0402")
      (description "电阻类型:厚膜电阻;阻值:11kΩ;精度:±1%;功率:62.5mW;最大工作电压:50V;温度系数:±100ppm/°C;")
      (fields
        (field (name "Manufacturer Part") "0603WAF1102T5E")
        (field (name "Manufacturer") "UNI-ROYAL(厚声)")
      )
      (libsource (lib "easyedapro") (part "0402WGF1102TCE"))
    )
    (comp (ref "R32")
      (value "11kΩ")
      (footprint "easyedapro:R0402")
      (description "电阻类型:厚膜电阻;阻值:11kΩ;精度:±1%;功率:62.5mW;最大工作电压:50V;温度系数:±100ppm/°C;")
      (fields
        (field (name "Manufacturer Part") "0603WAF1102T5E")
        (field (name "Manufacturer") "UNI-ROYAL(厚声)")
      )
      (libsource (lib "easyedapro") (part "0402WGF1102TCE"))
    )
    (comp (ref "R33")
      (value "11kΩ")
      (footprint "easyedapro:R0402")
      (description "电阻类型:厚膜电阻;阻值:11kΩ;精度:±1%;功率:62.5mW;最大工作电压:50V;温度系数:±100ppm/°C;")
      (fields
        (field (name "Manufacturer Part") "0603WAF1102T5E")
        (field (name "Manufacturer") "UNI-ROYAL(厚声)")
      )
      (libsource (lib "easyedapro") (part "0402WGF1102TCE"))
    )
    (comp (ref "R34")
      (value "11kΩ")
      (footprint "easyedapro:R0402")
      (description "电阻类型:厚膜电阻;阻值:11kΩ;精度:±1%;功率:62.5mW;最大工作电压:50V;温度系数:±100ppm/°C;")
      (fields
        (field (name "Manufacturer Part") "0603WAF1102T5E")
        (field (name "Manufacturer") "UNI-ROYAL(厚声)")
      )
      (libsource (lib "easyedapro") (part "0402WGF1102TCE"))
    )
    (comp (ref "R35")
      (value "10kΩ")
      (footprint "easyedapro:R0603")
      (description "电阻类型:厚膜电阻;阻值:10kΩ;精度:±1%;功率:100mW;最大工作电压:-;温度系数:±100ppm/°C;")
      (fields
        (field (name "Manufacturer Part") "0603WAF1002T5E")
        (field (name "Manufacturer") "UNI-ROYAL(厚声)")
      )
      (libsource (lib "easyedapro") (part "ERJ-3EKF1002V"))
    )
    (comp (ref "R36")
      (value "10kΩ")
      (footprint "easyedapro:R0603")
      (description "电阻类型:厚膜电阻;阻值:10kΩ;精度:±1%;功率:100mW;最大工作电压:-;温度系数:±100ppm/°C;")
      (fields
        (field (name "Manufacturer Part") "0603WAF1002T5E")
        (field (name "Manufacturer") "UNI-ROYAL(厚声)")
      )
      (libsource (lib "easyedapro") (part "ERJ-3EKF1002V"))
    )
    (comp (ref "R37")
      (value "100Ω")
      (footprint "easyedapro:R0603")
      (description "电阻类型:厚膜电阻;阻值:100Ω;精度:±1%;功率:100mW;最大工作电压:-;温度系数:±100ppm/°C;")
      (fields
        (field (name "Manufacturer Part") "0603WAF1000T5E")
        (field (name "Manufacturer") "UNI-ROYAL(厚声)")
      )
      (libsource (lib "easyedapro") (part "ERJ3EKF1000V"))
    )
    (comp (ref "R38")
      (value "100Ω")
      (footprint "easyedapro:R0603")
      (description "电阻类型:厚膜电阻;阻值:100Ω;精度:±1%;功率:100mW;最大工作电压:-;温度系数:±100ppm/°C;")
      (fields
        (field (name "Manufacturer Part") "0603WAF1000T5E")
        (field (name "Manufacturer") "UNI-ROYAL(厚声)")
      )
      (libsource (lib "easyedapro") (part "ERJ3EKF1000V"))
    )
    (comp (ref "R39")
      (value "100Ω")
      (footprint "easyedapro:R0603")
      (description "电阻类型:厚膜电阻;阻值:100Ω;精度:±1%;功率:100mW;最大工作电压:-;温度系数:±100ppm/°C;")
      (fields
        (field (name "Manufacturer Part") "0603WAF1000T5E")
        (field (name "Manufacturer") "UNI-ROYAL(厚声)")
      )
      (libsource (lib "easyedapro") (part "ERJ3EKF1000V"))
    )
    (comp (ref "U4")
      (value "STM32F407VGT6")
      (footprint "easyedapro:LQFP-100_L14.0-W14.0-P0.50-LS16.0-BL")
      (description "CPU内核:CM4;程序存储容量:1MB;RAM总容量:192KB;GPIO端口数量:82;工作电压范围:1.8V~3.6V;CPU最大主频:168MHz;程序存储器类型:FLASH;")
      (fields (field (name "Manufacturer") "ST(意法半导体)"))
      (libsource (lib "easyedapro") (part "STM32F407VGT6"))
    )
    (comp (ref "X2")
      (value "16MHz")
      (footprint "easyedapro:OSC-SMD_4P-L3.2-W2.5-BL")
      (description "晶振类型:贴片晶振;频率:16MHz;常温频差:±10ppm;外接负载电容:9pF;频率稳定度(全温):±20ppm;")
      (fields (field (name "Manufacturer Part") "X322516MLB4SI") (field (name "Manufacturer") "YXC(扬兴晶振)"))
      (libsource (lib "easyedapro") (part "X322516MLB4SI"))
    )
    (comp (ref "C61")
      (value "1uF")
      (footprint "easyedapro:C0603")
      (description "容值:1uF;精度:±10%;额定电压:50V;材质(温度系数):X5R;")
      (fields
        (field (name "Manufacturer Part") "CL10A105KB8NNNC")
        (field (name "Manufacturer") "SAMSUNG(三星)")
      )
      (libsource (lib "easyedapro") (part "CL10A105KB8NNNC"))
    )
    (comp (ref "C62")
      (value "10uF")
      (footprint "easyedapro:C0603")
      (description "容值:10uF;精度:±20%;额定电压:6.3V;材质(温度系数):X5R;")
      (fields
        (field (name "Manufacturer Part") "CL10A106KP8NNNC")
        (field (name "Manufacturer") "SAMSUNG(三星)")
      )
      (libsource (lib "easyedapro") (part "CL10A106MQ8NNNC"))
    )
    (comp (ref "C63")
      (value "2.2uF")
      (footprint "easyedapro:C0402")
      (description "容值:2.2uF;精度:±20%;额定电压:6.3V;材质(温度系数):X5R;")
      (fields
        (field (name "Manufacturer Part") "CL05A225MQ5NSNC")
        (field (name "Manufacturer") "SAMSUNG(三星)")
      )
      (libsource (lib "easyedapro") (part "CL05A225MQ5NSNC"))
    )
    (comp (ref "C64")
      (value "10uF")
      (footprint "easyedapro:C0603")
      (description "容值:10uF;精度:±20%;额定电压:6.3V;材质(温度系数):X5R;")
      (fields
        (field (name "Manufacturer Part") "CL10A106KP8NNNC")
        (field (name "Manufacturer") "SAMSUNG(三星)")
      )
      (libsource (lib "easyedapro") (part "CL10A106MQ8NNNC"))
    )
    (comp (ref "C65")
      (value "10uF")
      (footprint "easyedapro:C0603")
      (description "容值:10uF;精度:±20%;额定电压:6.3V;材质(温度系数):X5R;")
      (fields
        (field (name "Manufacturer Part") "CL10A106KP8NNNC")
        (field (name "Manufacturer") "SAMSUNG(三星)")
      )
      (libsource (lib "easyedapro") (part "CL10A106MQ8NNNC"))
    )
    (comp (ref "C66")
      (value "1uF")
      (footprint "easyedapro:C0603")
      (description "容值:1uF;精度:±10%;额定电压:50V;材质(温度系数):X5R;")
      (fields
        (field (name "Manufacturer Part") "CL10A105KB8NNNC")
        (field (name "Manufacturer") "SAMSUNG(三星)")
      )
      (libsource (lib "easyedapro") (part "CL10A105KB8NNNC"))
    )
    (comp (ref "C67")
      (value "1uF")
      (footprint "easyedapro:C0603")
      (description "容值:1uF;精度:±10%;额定电压:50V;材质(温度系数):X5R;")
      (fields
        (field (name "Manufacturer Part") "CL10A105KB8NNNC")
        (field (name "Manufacturer") "SAMSUNG(三星)")
      )
      (libsource (lib "easyedapro") (part "CL10A105KB8NNNC"))
    )
    (comp (ref "C68")
      (value "1uF")
      (footprint "easyedapro:C0603")
      (description "容值:1uF;精度:±10%;额定电压:50V;材质(温度系数):X5R;")
      (fields
        (field (name "Manufacturer Part") "CL10A105KB8NNNC")
        (field (name "Manufacturer") "SAMSUNG(三星)")
      )
      (libsource (lib "easyedapro") (part "CL10A105KB8NNNC"))
    )
    (comp (ref "C69")
      (value "2.2uF")
      (footprint "easyedapro:C0402")
      (description "容值:2.2uF;精度:±20%;额定电压:6.3V;材质(温度系数):X5R;")
      (fields
        (field (name "Manufacturer Part") "CL05A225MQ5NSNC")
        (field (name "Manufacturer") "SAMSUNG(三星)")
      )
      (libsource (lib "easyedapro") (part "CL05A225MQ5NSNC"))
    )
    (comp (ref "C70")
      (value "10uF")
      (footprint "easyedapro:C0603")
      (description "容值:10uF;精度:±20%;额定电压:6.3V;材质(温度系数):X5R;")
      (fields
        (field (name "Manufacturer Part") "CL10A106KP8NNNC")
        (field (name "Manufacturer") "SAMSUNG(三星)")
      )
      (libsource (lib "easyedapro") (part "CL10A106MQ8NNNC"))
    )
    (comp (ref "C71")
      (value "10uF")
      (footprint "easyedapro:C0603")
      (description "容值:10uF;精度:±20%;额定电压:6.3V;材质(温度系数):X5R;")
      (fields
        (field (name "Manufacturer Part") "CL10A106KP8NNNC")
        (field (name "Manufacturer") "SAMSUNG(三星)")
      )
      (libsource (lib "easyedapro") (part "CL10A106MQ8NNNC"))
    )
    (comp (ref "C72")
      (value "10uF")
      (footprint "easyedapro:C0603")
      (description "容值:10uF;精度:±20%;额定电压:6.3V;材质(温度系数):X5R;")
      (fields
        (field (name "Manufacturer Part") "CL10A106KP8NNNC")
        (field (name "Manufacturer") "SAMSUNG(三星)")
      )
      (libsource (lib "easyedapro") (part "CL10A106MQ8NNNC"))
    )
    (comp (ref "C73")
      (value "1uF")
      (footprint "easyedapro:C0603")
      (description "容值:1uF;精度:±10%;额定电压:50V;材质(温度系数):X5R;")
      (fields
        (field (name "Manufacturer Part") "CL10A105KB8NNNC")
        (field (name "Manufacturer") "SAMSUNG(三星)")
      )
      (libsource (lib "easyedapro") (part "CL10A105KB8NNNC"))
    )
    (comp (ref "C74")
      (value "1uF")
      (footprint "easyedapro:C0603")
      (description "容值:1uF;精度:±10%;额定电压:50V;材质(温度系数):X5R;")
      (fields
        (field (name "Manufacturer Part") "CL10A105KB8NNNC")
        (field (name "Manufacturer") "SAMSUNG(三星)")
      )
      (libsource (lib "easyedapro") (part "CL10A105KB8NNNC"))
    )
    (comp (ref "C75")
      (value "1uF")
      (footprint "easyedapro:C0603")
      (description "容值:1uF;精度:±10%;额定电压:50V;材质(温度系数):X5R;")
      (fields
        (field (name "Manufacturer Part") "CL10A105KB8NNNC")
        (field (name "Manufacturer") "SAMSUNG(三星)")
      )
      (libsource (lib "easyedapro") (part "CL10A105KB8NNNC"))
    )
    (comp (ref "C76")
      (value "10uF")
      (footprint "easyedapro:C0603")
      (description "容值:10uF;精度:±20%;额定电压:6.3V;材质(温度系数):X5R;")
      (fields
        (field (name "Manufacturer Part") "CL10A106KP8NNNC")
        (field (name "Manufacturer") "SAMSUNG(三星)")
      )
      (libsource (lib "easyedapro") (part "CL10A106MQ8NNNC"))
    )
    (comp (ref "C77")
      (value "1uF")
      (footprint "easyedapro:C0603")
      (description "容值:1uF;精度:±10%;额定电压:50V;材质(温度系数):X5R;")
      (fields
        (field (name "Manufacturer Part") "CL10A105KB8NNNC")
        (field (name "Manufacturer") "SAMSUNG(三星)")
      )
      (libsource (lib "easyedapro") (part "CL10A105KB8NNNC"))
    )
    (comp (ref "C78")
      (value "10uF")
      (footprint "easyedapro:C0603")
      (description "容值:10uF;精度:±20%;额定电压:6.3V;材质(温度系数):X5R;")
      (fields
        (field (name "Manufacturer Part") "CL10A106KP8NNNC")
        (field (name "Manufacturer") "SAMSUNG(三星)")
      )
      (libsource (lib "easyedapro") (part "CL10A106MQ8NNNC"))
    )
    (comp (ref "C79")
      (value "10uF")
      (footprint "easyedapro:C0603")
      (description "容值:10uF;精度:±20%;额定电压:6.3V;材质(温度系数):X5R;")
      (fields
        (field (name "Manufacturer Part") "CL10A106KP8NNNC")
        (field (name "Manufacturer") "SAMSUNG(三星)")
      )
      (libsource (lib "easyedapro") (part "CL10A106MQ8NNNC"))
    )
    (comp (ref "C80")
      (value "1uF")
      (footprint "easyedapro:C0603")
      (description "容值:1uF;精度:±10%;额定电压:50V;材质(温度系数):X5R;")
      (fields
        (field (name "Manufacturer Part") "CL10A105KB8NNNC")
        (field (name "Manufacturer") "SAMSUNG(三星)")
      )
      (libsource (lib "easyedapro") (part "CL10A105KB8NNNC"))
    )
    (comp (ref "C81")
      (value "2.2uF")
      (footprint "easyedapro:C0402")
      (description "容值:2.2uF;精度:±20%;额定电压:6.3V;材质(温度系数):X5R;")
      (fields
        (field (name "Manufacturer Part") "CL05A225MQ5NSNC")
        (field (name "Manufacturer") "SAMSUNG(三星)")
      )
      (libsource (lib "easyedapro") (part "CL05A225MQ5NSNC"))
    )
    (comp (ref "C82")
      (value "10nF")
      (footprint "easyedapro:C0603")
      (description "容值:10nF;精度:±10%;额定电压:50V;材质(温度系数):X7R;")
      (fields (field (name "Manufacturer Part") "0603B103K500NT") (field (name "Manufacturer") "FH(风华)"))
      (libsource (lib "easyedapro") (part "CC0603KRX7R9BB103"))
    )
    (comp (ref "C83")
      (value "2.2uF")
      (footprint "easyedapro:C0402")
      (description "容值:2.2uF;精度:±20%;额定电压:6.3V;材质(温度系数):X5R;")
      (fields
        (field (name "Manufacturer Part") "CL05A225MQ5NSNC")
        (field (name "Manufacturer") "SAMSUNG(三星)")
      )
      (libsource (lib "easyedapro") (part "CL05A225MQ5NSNC"))
    )
    (comp (ref "C84")
      (value "10uF")
      (footprint "easyedapro:C0603")
      (description "容值:10uF;精度:±20%;额定电压:6.3V;材质(温度系数):X5R;")
      (fields
        (field (name "Manufacturer Part") "CL10A106KP8NNNC")
        (field (name "Manufacturer") "SAMSUNG(三星)")
      )
      (libsource (lib "easyedapro") (part "CL10A106MQ8NNNC"))
    )
    (comp (ref "LED4")
      (value "KT-0603W")
      (footprint "easyedapro:LED0603-R-RD_GREEN")
      (fields (field (name "Manufacturer") "KENTO"))
      (libsource (lib "easyedapro") (part "HL-PST-1608U51GC"))
    )
    (comp (ref "LED5")
      (value "KT-0805G")
      (footprint "easyedapro:LED0805-RD_RED")
      (fields (field (name "Manufacturer") "KENTO"))
      (libsource (lib "easyedapro") (part "HL-PC-2012S52FC-L"))
    )
    (comp (ref "LED6")
      (value "KT-0805G")
      (footprint "easyedapro:LED0805-RD_RED")
      (fields (field (name "Manufacturer") "KENTO"))
      (libsource (lib "easyedapro") (part "HL-PC-2012S52FC-L"))
    )
    (comp (ref "LED7")
      (value "KT-0603W")
      (footprint "easyedapro:LED0603-R-RD_GREEN")
      (fields (field (name "Manufacturer") "KENTO"))
      (libsource (lib "easyedapro") (part "HL-PST-1608U51GC"))
    )
    (comp (ref "R41")
      (value "10kΩ")
      (footprint "easyedapro:R0603")
      (description "电阻类型:厚膜电阻;阻值:10kΩ;精度:±1%;功率:100mW;最大工作电压:-;温度系数:±100ppm/°C;")
      (fields
        (field (name "Manufacturer Part") "0603WAF1002T5E")
        (field (name "Manufacturer") "UNI-ROYAL(厚声)")
      )
      (libsource (lib "easyedapro") (part "ERJ-3EKF1002V"))
    )
    (comp (ref "R42")
      (value "10kΩ")
      (footprint "easyedapro:R0603")
      (description "电阻类型:厚膜电阻;阻值:10kΩ;精度:±1%;功率:100mW;最大工作电压:-;温度系数:±100ppm/°C;")
      (fields
        (field (name "Manufacturer Part") "0603WAF1002T5E")
        (field (name "Manufacturer") "UNI-ROYAL(厚声)")
      )
      (libsource (lib "easyedapro") (part "ERJ-3EKF1002V"))
    )
    (comp (ref "R43")
      (value "10kΩ")
      (footprint "easyedapro:R0603")
      (description "电阻类型:厚膜电阻;阻值:10kΩ;精度:±1%;功率:100mW;最大工作电压:-;温度系数:±100ppm/°C;")
      (fields
        (field (name "Manufacturer Part") "0603WAF1002T5E")
        (field (name "Manufacturer") "UNI-ROYAL(厚声)")
      )
      (libsource (lib "easyedapro") (part "ERJ-3EKF1002V"))
    )
    (comp (ref "R44")
      (value "10kΩ")
      (footprint "easyedapro:R0603")
      (description "电阻类型:厚膜电阻;阻值:10kΩ;精度:±1%;功率:100mW;最大工作电压:-;温度系数:±100ppm/°C;")
      (fields
        (field (name "Manufacturer Part") "0603WAF1002T5E")
        (field (name "Manufacturer") "UNI-ROYAL(厚声)")
      )
      (libsource (lib "easyedapro") (part "ERJ-3EKF1002V"))
    )
    (comp (ref "SCREW1")
      (value "~")
      (footprint "easyedapro:M3螺丝")
      (libsource (lib "easyedapro") (part "螺丝孔"))
    )
    (comp (ref "SCREW2")
      (value "~")
      (footprint "easyedapro:M3螺丝")
      (libsource (lib "easyedapro") (part "螺丝孔"))
    )
    (comp (ref "SCREW3")
      (value "~")
      (footprint "easyedapro:M3螺丝")
      (libsource (lib "easyedapro") (part "螺丝孔"))
    )
    (comp (ref "SCREW4")
      (value "~")
      (footprint "easyedapro:M3螺丝")
      (libsource (lib "easyedapro") (part "螺丝孔"))
    )
    (comp (ref "U5")
      (value "TPS60403DBVR")
      (footprint "easyedapro:SOT-23-5_L3.0-W1.7-P0.95-LS2.8-BR")
      (description "功能类型:-;输出类型:固定;输入电压:1.8V~5.25V;输出电压:-5.5V~-1.6V;输出电流(最大值):60mA;")
      (fields (field (name "Manufacturer") "TI(德州仪器)"))
      (libsource (lib "easyedapro") (part "TPS60403DBVR"))
    )
    (comp (ref "U6")
      (value "TPS72325DBVR")
      (footprint "easyedapro:SOT-23-5_L3.0-W1.7-P0.95-LS2.8-BR")
      (description "输出类型:固定;最大输入电压:10V;输出电压:2.5V;最大输出电流:200mA;电源纹波抑制比(PSRR):65dB;输出极性:负极;")
      (fields (field (name "Manufacturer") "TI(德州仪器)"))
      (libsource (lib "easyedapro") (part "TPS72325DBVR"))
    )
    (comp (ref "U7")
      (value "TPS73233DBVR")
      (footprint "easyedapro:SOT-23-5_L3.0-W1.7-P0.95-LS2.8-BL")
      (description "输出类型:固定;最大输入电压:5.5V;输出电压:3.3V;最大输出电流:250mA;电源纹波抑制比(PSRR):58dB;输出极性:正极;")
      (fields (field (name "Manufacturer") "TI(德州仪器)"))
      (libsource (lib "easyedapro") (part "TPS73233DBVR"))
    )
    (comp (ref "U8")
      (value "TPS73225DBVR")
      (footprint "easyedapro:SOT-23-5_L2.9-W1.6-P0.95-LS2.8-TL")
      (description "输出类型:固定;最大输入电压:5.5V;输出电压:2.5V;最大输出电流:250mA;输出极性:正极;")
      (fields (field (name "Manufacturer") "TI(德州仪器)"))
      (libsource (lib "easyedapro") (part "TPS73225DBVR"))
    )
  )
  (nets
    (net (code "1") (name "AVDD") (class "Default")
      (node (ref "C100") (pin "1") (pinfunction "1_1") (pintype "input"))
      (node (ref "C101") (pin "1") (pinfunction "1_1") (pintype "unspecified"))
      (node (ref "C102") (pin "1") (pinfunction "1_1") (pintype "unspecified"))
      (node (ref "C68") (pin "2") (pinfunction "2_2") (pintype "input"))
      (node (ref "C69") (pin "2") (pinfunction "2_2") (pintype "unspecified"))
      (node (ref "C70") (pin "1") (pinfunction "1_1") (pintype "unspecified"))
      (node (ref "C99") (pin "1") (pinfunction "1_1") (pintype "input"))
      (node (ref "H5") (pin "3") (pinfunction "3_3") (pintype "unspecified"))
      (node (ref "H5") (pin "4") (pinfunction "4_4") (pintype "unspecified"))
      (node (ref "R42") (pin "2") (pinfunction "2_2") (pintype "unspecified"))
      (node (ref "U2") (pin "19") (pinfunction "AVDD_19") (pintype "unspecified"))
      (node (ref "U2") (pin "21") (pinfunction "AVDD_21") (pintype "unspecified"))
      (node (ref "U2") (pin "22") (pinfunction "AVDD_22") (pintype "unspecified"))
      (node (ref "U2") (pin "54") (pinfunction "AVDD1_54") (pintype "unspecified"))
      (node (ref "U2") (pin "56") (pinfunction "AVDD_56") (pintype "unspecified"))
      (node (ref "U2") (pin "59") (pinfunction "AVDD_59") (pintype "unspecified"))
      (node (ref "U8") (pin "5") (pinfunction "OUT_5") (pintype "input"))
    )
    (net (code "2") (name "AVSS") (class "Default")
      (node (ref "C103") (pin "1") (pinfunction "1_1") (pintype "unspecified"))
      (node (ref "C104") (pin "1") (pinfunction "1_1") (pintype "unspecified"))
      (node (ref "C105") (pin "1") (pinfunction "1_1") (pintype "unspecified"))
      (node (ref "C11") (pin "2") (pinfunction "2_2") (pintype "input"))
      (node (ref "C12") (pin "1") (pinfunction "1_1") (pintype "input"))
      (node (ref "C14") (pin "1") (pinfunction "1_1") (pintype "unspecified"))
      (node (ref "C15") (pin "2") (pinfunction "2_2") (pintype "input"))
      (node (ref "C6") (pin "1") (pinfunction "1_1") (pintype "input"))
      (node (ref "C7") (pin "1") (pinfunction "1_1") (pintype "input"))
      (node (ref "C79") (pin "1") (pinfunction "1_1") (pintype "unspecified"))
      (node (ref "C80") (pin "2") (pinfunction "2_2") (pintype "input"))
      (node (ref "C81") (pin "2") (pinfunction "2_2") (pintype "unspecified"))
      (node (ref "C87") (pin "2") (pinfunction "2_2") (pintype "input"))
      (node (ref "C88") (pin "2") (pinfunction "2_2") (pintype "input"))
      (node (ref "H5") (pin "1") (pinfunction "1_1") (pintype "unspecified"))
      (node (ref "H5") (pin "2") (pinfunction "2_2") (pintype "unspecified"))
      (node (ref "LED6") (pin "2") (pinfunction "A_2") (pintype "unspecified"))
      (node (ref "U2") (pin "20") (pinfunction "AVSS_20") (pintype "unspecified"))
      (node (ref "U2") (pin "23") (pinfunction "AVSS_23") (pintype "unspecified"))
      (node (ref "U2") (pin "25") (pinfunction "VREFN_25") (pintype "unspecified"))
      (node (ref "U2") (pin "32") (pinfunction "AVSS_32") (pintype "unspecified"))
      (node (ref "U2") (pin "53") (pinfunction "AVSS1_53") (pintype "unspecified"))
      (node (ref "U2") (pin "57") (pinfunction "AVSS_57") (pintype "unspecified"))
      (node (ref "U2") (pin "58") (pinfunction "AVSS_58") (pintype "unspecified"))
      (node (ref "U6") (pin "5") (pinfunction "OUT_5") (pintype "unspecified"))
    )
    (net (code "3") (name "BIAS_INV") (class "Default")
      (node (ref "C18") (pin "1") (pinfunction "1_1") (pintype "input"))
      (node (ref "H6") (pin "1") (pinfunction "1_1") (pintype "input"))
      (node (ref "R6") (pin "1") (pinfunction "1_1") (pintype "unspecified"))
      (node (ref "U2") (pin "61") (pinfunction "BIASINV_61") (pintype "unspecified"))
    )
    (net (code "4") (name "BIAS_OUT") (class "Default")
      (node (ref "C18") (pin "2") (pinfunction "2_2") (pintype "input"))
      (node (ref "C44") (pin "2") (pinfunction "2_2") (pintype "input"))
      (node (ref "R34") (pin "2") (pinfunction "2_2") (pintype "input"))
      (node (ref "R6") (pin "2") (pinfunction "2_2") (pintype "unspecified"))
      (node (ref "U2") (pin "62") (pinfunction "BIASIN_62") (pintype "unspecified"))
      (node (ref "U2") (pin "63") (pinfunction "BIASOUT_63") (pintype "unspecified"))
    )
    (net (code "5") (name "CBIAS") (class "Default")
      (node (ref "H6") (pin "2") (pinfunction "2_2") (pintype "input"))
      (node (ref "R34") (pin "1") (pinfunction "1_1") (pintype "input"))
    )
    (net (code "6") (name "CIN1N") (class "Default")
      (node (ref "H7") (pin "4") (pinfunction "4_4") (pintype "input"))
      (node (ref "R16") (pin "1") (pinfunction "1_1") (pintype "input"))
    )
    (net (code "7") (name "CIN1P") (class "Default")
      (node (ref "H7") (pin "3") (pinfunction "3_3") (pintype "input"))
      (node (ref "R17") (pin "1") (pinfunction "1_1") (pintype "input"))
    )
    (net (code "8") (name "CIN2N") (class "Default")
      (node (ref "H7") (pin "6") (pinfunction "6_6") (pintype "input"))
      (node (ref "R18") (pin "1") (pinfunction "1_1") (pintype "input"))
    )
    (net (code "9") (name "CIN2P") (class "Default")
      (node (ref "H7") (pin "5") (pinfunction "5_5") (pintype "input"))
      (node (ref "R19") (pin "1") (pinfunction "1_1") (pintype "input"))
    )
    (net (code "10") (name "CIN3N") (class "Default")
      (node (ref "H7") (pin "8") (pinfunction "8_8") (pintype "input"))
      (node (ref "R20") (pin "1") (pinfunction "1_1") (pintype "input"))
    )
    (net (code "11") (name "CIN3P") (class "Default")
      (node (ref "H7") (pin "7") (pinfunction "7_7") (pintype "input"))
      (node (ref "R21") (pin "1") (pinfunction "1_1") (pintype "input"))
    )
    (net (code "12") (name "CIN4N") (class "Default")
      (node (ref "H7") (pin "10") (pinfunction "10_10") (pintype "input"))
      (node (ref "R22") (pin "1") (pinfunction "1_1") (pintype "input"))
    )
    (net (code "13") (name "CIN4P") (class "Default")
      (node (ref "H7") (pin "9") (pinfunction "9_9") (pintype "input"))
      (node (ref "R23") (pin "1") (pinfunction "1_1") (pintype "input"))
    )
    (net (code "14") (name "CIN5N") (class "Default")
      (node (ref "H6") (pin "9") (pinfunction "9_9") (pintype "input"))
      (node (ref "R26") (pin "1") (pinfunction "1_1") (pintype "input"))
    )
    (net (code "15") (name "CIN5P") (class "Default")
      (node (ref "H6") (pin "10") (pinfunction "10_10") (pintype "input"))
      (node (ref "R27") (pin "1") (pinfunction "1_1") (pintype "input"))
    )
    (net (code "16") (name "CIN6N") (class "Default")
      (node (ref "H6") (pin "7") (pinfunction "7_7") (pintype "input"))
      (node (ref "R28") (pin "1") (pinfunction "1_1") (pintype "input"))
    )
    (net (code "17") (name "CIN6P") (class "Default")
      (node (ref "H6") (pin "8") (pinfunction "8_8") (pintype "input"))
      (node (ref "R29") (pin "1") (pinfunction "1_1") (pintype "input"))
    )
    (net (code "18") (name "CIN7N") (class "Default")
      (node (ref "H6") (pin "5") (pinfunction "5_5") (pintype "input"))
      (node (ref "R30") (pin "1") (pinfunction "1_1") (pintype "input"))
    )
    (net (code "19") (name "CIN7P") (class "Default")
      (node (ref "H6") (pin "6") (pinfunction "6_6") (pintype "input"))
      (node (ref "R31") (pin "1") (pinfunction "1_1") (pintype "input"))
    )
    (net (code "20") (name "CIN8N") (class "Default")
      (node (ref "H6") (pin "3") (pinfunction "3_3") (pintype "input"))
      (node (ref "R24") (pin "1") (pinfunction "1_1") (pintype "input"))
    )
    (net (code "21") (name "CIN8P") (class "Default")
      (node (ref "H6") (pin "4") (pinfunction "4_4") (pintype "input"))
      (node (ref "R25") (pin "1") (pinfunction "1_1") (pintype "input"))
    )
    (net (code "22") (name "CLK") (class "Default")
      (node (ref "H4") (pin "3") (pinfunction "3_3") (pintype "unspecified"))
      (node (ref "U2") (pin "37") (pinfunction "CLK_37") (pintype "unspecified"))
      (node (ref "X1") (pin "3") (pinfunction "OUTPUT_3") (pintype "unspecified"))
    )
    (net (code "23") (name "CS") (class "Default")
      (node (ref "H4") (pin "7") (pinfunction "7_7") (pintype "unspecified"))
      (node (ref "U2") (pin "39") (pinfunction "CS#_39") (pintype "unspecified"))
      (node (ref "U4") (pin "88") (pinfunction "PD7_88") (pintype "unspecified"))
    )
    (net (code "24") (name "CSRB1") (class "Default")
      (node (ref "H7") (pin "2") (pinfunction "2_2") (pintype "input"))
      (node (ref "R32") (pin "1") (pinfunction "1_1") (pintype "input"))
    )
    (net (code "25") (name "CSRB2") (class "Default")
      (node (ref "H7") (pin "1") (pinfunction "1_1") (pintype "input"))
      (node (ref "R33") (pin "1") (pinfunction "1_1") (pintype "input"))
    )
    (net (code "26") (name "DRDY") (class "Default")
      (node (ref "H4") (pin "9") (pinfunction "9_9") (pintype "unspecified"))
      (node (ref "U2") (pin "47") (pinfunction "DRDY#_47") (pintype "unspecified"))
      (node (ref "U4") (pin "87") (pinfunction "PD6_87") (pintype "unspecified"))
    )
    (net (code "27") (name "DVDD") (class "Default")
      (node (ref "C45") (pin "2") (pinfunction "2_2") (pintype "input"))
      (node (ref "C46") (pin "2") (pinfunction "2_2") (pintype "unspecified"))
      (node (ref "C52") (pin "1") (pinfunction "1_1") (pintype "unspecified"))
      (node (ref "C53") (pin "2") (pinfunction "2_2") (pintype "unspecified"))
      (node (ref "C56") (pin "2") (pinfunction "2_2") (pintype "unspecified"))
      (node (ref "C62") (pin "1") (pinfunction "1_1") (pintype "unspecified"))
      (node (ref "C63") (pin "2") (pinfunction "2_2") (pintype "unspecified"))
      (node (ref "C85") (pin "1") (pinfunction "1_1") (pintype "input"))
      (node (ref "C89") (pin "2") (pinfunction "2_2") (pintype "input"))
      (node (ref "C90") (pin "1") (pinfunction "1_1") (pintype "unspecified"))
      (node (ref "C91") (pin "1") (pinfunction "1_1") (pintype "unspecified"))
      (node (ref "C92") (pin "1") (pinfunction "1_1") (pintype "unspecified"))
      (node (ref "C93") (pin "1") (pinfunction "1_1") (pintype "unspecified"))
      (node (ref "C94") (pin "1") (pinfunction "1_1") (pintype "unspecified"))
      (node (ref "C95") (pin "2") (pinfunction "2_2") (pintype "input"))
      (node (ref "C96") (pin "1") (pinfunction "1_1") (pintype "unspecified"))
      (node (ref "C97") (pin "1") (pinfunction "1_1") (pintype "input"))
      (node (ref "C98") (pin "1") (pinfunction "1_1") (pintype "unspecified"))
      (node (ref "H2") (pin "6") (pinfunction "6_6") (pintype "unspecified"))
      (node (ref "H5") (pin "5") (pinfunction "5_5") (pintype "unspecified"))
      (node (ref "H5") (pin "6") (pinfunction "6_6") (pintype "unspecified"))
      (node (ref "R41") (pin "2") (pinfunction "2_2") (pintype "unspecified"))
      (node (ref "R8") (pin "2") (pinfunction "2_2") (pintype "unspecified"))
      (node (ref "R9") (pin "2") (pinfunction "2_2") (pintype "unspecified"))
      (node (ref "U10") (pin "6") (pinfunction "6_6") (pintype "unspecified"))
      (node (ref "U2") (pin "48") (pinfunction "DVDD_48") (pintype "unspecified"))
      (node (ref "U2") (pin "50") (pinfunction "DVDD_50") (pintype "unspecified"))
      (node (ref "U4") (pin "100") (pinfunction "VDD_100") (pintype "unspecified"))
      (node (ref "U4") (pin "11") (pinfunction "VDD_11") (pintype "unspecified"))
      (node (ref "U4") (pin "19") (pinfunction "VDD_19") (pintype "unspecified"))
      (node (ref "U4") (pin "21") (pinfunction "VREF+_21") (pintype "unspecified"))
      (node (ref "U4") (pin "22") (pinfunction "VDDA_22") (pintype "unspecified"))
      (node (ref "U4") (pin "28") (pinfunction "VDD_28") (pintype "unspecified"))
      (node (ref "U4") (pin "50") (pinfunction "VDD_50") (pintype "unspecified"))
      (node (ref "U4") (pin "6") (pinfunction "VBAT_6") (pintype "unspecified"))
      (node (ref "U4") (pin "75") (pinfunction "VDD_75") (pintype "unspecified"))
      (node (ref "U7") (pin "5") (pinfunction "OUT_5") (pintype "input"))
      (node (ref "U9") (pin "7") (pinfunction "7_7") (pintype "unspecified"))
      (node (ref "X1") (pin "1") (pinfunction "OE_1") (pintype "unspecified"))
      (node (ref "X1") (pin "4") (pinfunction "VDD_4") (pintype "unspecified"))
    )
    (net (code "28") (name "GND") (class "Default")
      (node (ref "C100") (pin "2") (pinfunction "2_2") (pintype "input"))
      (node (ref "C101") (pin "2") (pinfunction "2_2") (pintype "unspecified"))
      (node (ref "C102") (pin "2") (pinfunction "2_2") (pintype "unspecified"))
      (node (ref "C103") (pin "2") (pinfunction "2_2") (pintype "unspecified"))
      (node (ref "C104") (pin "2") (pinfunction "2_2") (pintype "unspecified"))
      (node (ref "C19") (pin "1") (pinfunction "1_1") (pintype "unspecified"))
      (node (ref "C26") (pin "1") (pinfunction "1_1") (pintype "input"))
      (node (ref "C27") (pin "2") (pinfunction "2_2") (pintype "input"))
      (node (ref "C28") (pin "1") (pinfunction "1_1") (pintype "input"))
      (node (ref "C29") (pin "2") (pinfunction "2_2") (pintype "input"))
      (node (ref "C30") (pin "1") (pinfunction "1_1") (pintype "input"))
      (node (ref "C31") (pin "2") (pinfunction "2_2") (pintype "input"))
      (node (ref "C32") (pin "1") (pinfunction "1_1") (pintype "input"))
      (node (ref "C33") (pin "2") (pinfunction "2_2") (pintype "input"))
      (node (ref "C34") (pin "1") (pinfunction "1_1") (pintype "input"))
      (node (ref "C35") (pin "2") (pinfunction "2_2") (pintype "input"))
      (node (ref "C36") (pin "1") (pinfunction "1_1") (pintype "input"))
      (node (ref "C37") (pin "2") (pinfunction "2_2") (pintype "input"))
      (node (ref "C38") (pin "1") (pinfunction "1_1") (pintype "input"))
      (node (ref "C39") (pin "2") (pinfunction "2_2") (pintype "input"))
      (node (ref "C40") (pin "1") (pinfunction "1_1") (pintype "input"))
      (node (ref "C41") (pin "2") (pinfunction "2_2") (pintype "input"))
      (node (ref "C42") (pin "1") (pinfunction "1_1") (pintype "input"))
      (node (ref "C43") (pin "2") (pinfunction "2_2") (pintype "input"))
      (node (ref "C44") (pin "1") (pinfunction "1_1") (pintype "input"))
      (node (ref "C45") (pin "1") (pinfunction "1_1") (pintype "input"))
      (node (ref "C46") (pin "1") (pinfunction "1_1") (pintype "unspecified"))
      (node (ref "C52") (pin "2") (pinfunction "2_2") (pintype "unspecified"))
      (node (ref "C53") (pin "1") (pinfunction "1_1") (pintype "unspecified"))
      (node (ref "C56") (pin "1") (pinfunction "1_1") (pintype "unspecified"))
      (node (ref "C57") (pin "2") (pinfunction "2_2") (pintype "input"))
      (node (ref "C58") (pin "2") (pinfunction "2_2") (pintype "input"))
      (node (ref "C59") (pin "1") (pinfunction "1_1") (pintype "unspecified"))
      (node (ref "C6") (pin "2") (pinfunction "2_2") (pintype "input"))
      (node (ref "C60") (pin "1") (pinfunction "1_1") (pintype "unspecified"))
      (node (ref "C61") (pin "1") (pinfunction "1_1") (pintype "input"))
      (node (ref "C62") (pin "2") (pinfunction "2_2") (pintype "unspecified"))
      (node (ref "C63") (pin "1") (pinfunction "1_1") (pintype "unspecified"))
      (node (ref "C64") (pin "2") (pinfunction "2_2") (pintype "unspecified"))
      (node (ref "C65") (pin "2") (pinfunction "2_2") (pintype "unspecified"))
      (node (ref "C66") (pin "1") (pinfunction "1_1") (pintype "input"))
      (node (ref "C67") (pin "1") (pinfunction "1_1") (pintype "input"))
      (node (ref "C68") (pin "1") (pinfunction "1_1") (pintype "input"))
      (node (ref "C69") (pin "1") (pinfunction "1_1") (pintype "unspecified"))
      (node (ref "C7") (pin "2") (pinfunction "2_2") (pintype "input"))
      (node (ref "C70") (pin "2") (pinfunction "2_2") (pintype "unspecified"))
      (node (ref "C71") (pin "2") (pinfunction "2_2") (pintype "unspecified"))
      (node (ref "C72") (pin "2") (pinfunction "2_2") (pintype "unspecified"))
      (node (ref "C73") (pin "1") (pinfunction "1_1") (pintype "input"))
      (node (ref "C75") (pin "1") (pinfunction "1_1") (pintype "input"))
      (node (ref "C76") (pin "2") (pinfunction "2_2") (pintype "unspecified"))
      (node (ref "C77") (pin "1") (pinfunction "1_1") (pintype "input"))
      (node (ref "C78") (pin "2") (pinfunction "2_2") (pintype "unspecified"))
      (node (ref "C79") (pin "2") (pinfunction "2_2") (pintype "unspecified"))
      (node (ref "C80") (pin "1") (pinfunction "1_1") (pintype "input"))
      (node (ref "C81") (pin "1") (pinfunction "1_1") (pintype "unspecified"))
      (node (ref "C82") (pin "1") (pinfunction "1_1") (pintype "input"))
      (node (ref "C83") (pin "1") (pinfunction "1_1") (pintype "unspecified"))
      (node (ref "C84") (pin "2") (pinfunction "2_2") (pintype "unspecified"))
      (node (ref "C85") (pin "2") (pinfunction "2_2") (pintype "input"))
      (node (ref "C89") (pin "1") (pinfunction "1_1") (pintype "input"))
      (node (ref "C90") (pin "2") (pinfunction "2_2") (pintype "unspecified"))
      (node (ref "C91") (pin "2") (pinfunction "2_2") (pintype "unspecified"))
      (node (ref "C92") (pin "2") (pinfunction "2_2") (pintype "unspecified"))
      (node (ref "C93") (pin "2") (pinfunction "2_2") (pintype "unspecified"))
      (node (ref "C94") (pin "2") (pinfunction "2_2") (pintype "unspecified"))
      (node (ref "C95") (pin "1") (pinfunction "1_1") (pintype "input"))
      (node (ref "C96") (pin "2") (pinfunction "2_2") (pintype "unspecified"))
      (node (ref "C97") (pin "2") (pinfunction "2_2") (pintype "input"))
      (node (ref "C98") (pin "2") (pinfunction "2_2") (pintype "unspecified"))
      (node (ref "C99") (pin "2") (pinfunction "2_2") (pintype "input"))
      (node (ref "H2") (pin "7") (pinfunction "7_7") (pintype "unspecified"))
      (node (ref "H2") (pin "8") (pinfunction "8_8") (pintype "unspecified"))
      (node (ref "H4") (pin "10") (pinfunction "10_10") (pintype "unspecified"))
      (node (ref "LED4") (pin "2") (pinfunction "K_2") (pintype "unspecified"))
      (node (ref "LED5") (pin "2") (pinfunction "A_2") (pintype "unspecified"))
      (node (ref "LED7") (pin "1") (pinfunction "A_1") (pintype "unspecified"))
      (node (ref "LED8") (pin "2") (pinfunction "K_2") (pintype "unspecified"))
      (node (ref "R35") (pin "2") (pinfunction "2_2") (pintype "unspecified"))
      (node (ref "R36") (pin "2") (pinfunction "2_2") (pintype "unspecified"))
      (node (ref "R37") (pin "1") (pinfunction "1_1") (pintype "unspecified"))
      (node (ref "R38") (pin "1") (pinfunction "1_1") (pintype "unspecified"))
      (node (ref "R39") (pin "1") (pinfunction "1_1") (pintype "unspecified"))
      (node (ref "R43") (pin "1") (pinfunction "1_1") (pintype "unspecified"))
      (node (ref "SW1") (pin "2") (pinfunction "2_2") (pintype "unspecified"))
      (node (ref "U10") (pin "1") (pinfunction "1_1") (pintype "unspecified"))
      (node (ref "U10") (pin "5") (pinfunction "5_5") (pintype "unspecified"))
      (node (ref "U2") (pin "31") (pinfunction "RESV1_31") (pintype "unspecified"))
      (node (ref "U2") (pin "33") (pinfunction "DGND_33") (pintype "unspecified"))
      (node (ref "U2") (pin "41") (pinfunction "DAISY_IN_41") (pintype "unspecified"))
      (node (ref "U2") (pin "45") (pinfunction "GPIO3_45") (pintype "unspecified"))
      (node (ref "U2") (pin "46") (pinfunction "GPIO4_46") (pintype "unspecified"))
      (node (ref "U2") (pin "49") (pinfunction "DGND_49") (pintype "unspecified"))
      (node (ref "U2") (pin "51") (pinfunction "DGND_51") (pintype "unspecified"))
      (node (ref "U2") (pin "52") (pinfunction "CLKSEL_52") (pintype "unspecified"))
      (node (ref "U2") (pin "60") (pinfunction "BIASREF_60") (pintype "unspecified"))
      (node (ref "U4") (pin "10") (pinfunction "VSS_10") (pintype "unspecified"))
      (node (ref "U4") (pin "20") (pinfunction "VSSA_20") (pintype "unspecified"))
      (node (ref "U4") (pin "27") (pinfunction "VSS_27") (pintype "unspecified"))
      (node (ref "U4") (pin "74") (pinfunction "VSS_74") (pintype "unspecified"))
      (node (ref "U4") (pin "99") (pinfunction "VSS_99") (pintype "unspecified"))
      (node (ref "U5") (pin "4") (pinfunction "GND_4") (pintype "input"))
      (node (ref "U6") (pin "1") (pinfunction "GND_1") (pintype "unspecified"))
      (node (ref "U7") (pin "2") (pinfunction "GND_2") (pintype "input"))
      (node (ref "U8") (pin "2") (pinfunction "GND_2") (pintype "input"))
      (node (ref "U9") (pin "4") (pinfunction "4_4") (pintype "unspecified"))
      (node (ref "USB2") (pin "A12") (pinfunction "GND_A12") (pintype "unspecified"))
      (node (ref "USB2") (pin "B12") (pinfunction "GND_B12") (pintype "unspecified"))
      (node (ref "X1") (pin "2") (pinfunction "GND_2") (pintype "unspecified"))
      (node (ref "X2") (pin "2") (pinfunction "GND_2") (pintype "unspecified"))
      (node (ref "X2") (pin "4") (pinfunction "GND_4") (pintype "unspecified"))
    )
    (net (code "29") (name "IN1N") (class "Default")
      (node (ref "C26") (pin "2") (pinfunction "2_2") (pintype "input"))
      (node (ref "R16") (pin "2") (pinfunction "2_2") (pintype "input"))
      (node (ref "U2") (pin "15") (pinfunction "IN1N_15") (pintype "unspecified"))
    )
    (net (code "30") (name "IN1P") (class "Default")
      (node (ref "C27") (pin "1") (pinfunction "1_1") (pintype "input"))
      (node (ref "R17") (pin "2") (pinfunction "2_2") (pintype "input"))
      (node (ref "U2") (pin "16") (pinfunction "IN1P_16") (pintype "unspecified"))
    )
    (net (code "31") (name "IN2N") (class "Default")
      (node (ref "C28") (pin "2") (pinfunction "2_2") (pintype "input"))
      (node (ref "R18") (pin "2") (pinfunction "2_2") (pintype "input"))
      (node (ref "U2") (pin "13") (pinfunction "IN2N_13") (pintype "unspecified"))
    )
    (net (code "32") (name "IN2P") (class "Default")
      (node (ref "C29") (pin "1") (pinfunction "1_1") (pintype "input"))
      (node (ref "R19") (pin "2") (pinfunction "2_2") (pintype "input"))
      (node (ref "U2") (pin "14") (pinfunction "IN2P_14") (pintype "unspecified"))
    )
    (net (code "33") (name "IN3N") (class "Default")
      (node (ref "C30") (pin "2") (pinfunction "2_2") (pintype "input"))
      (node (ref "R20") (pin "2") (pinfunction "2_2") (pintype "input"))
      (node (ref "U2") (pin "11") (pinfunction "IN3N_11") (pintype "unspecified"))
    )
    (net (code "34") (name "IN3P") (class "Default")
      (node (ref "C31") (pin "1") (pinfunction "1_1") (pintype "input"))
      (node (ref "R21") (pin "2") (pinfunction "2_2") (pintype "input"))
      (node (ref "U2") (pin "12") (pinfunction "IN3P_12") (pintype "unspecified"))
    )
    (net (code "35") (name "IN4N") (class "Default")
      (node (ref "C32") (pin "2") (pinfunction "2_2") (pintype "input"))
      (node (ref "R22") (pin "2") (pinfunction "2_2") (pintype "input"))
      (node (ref "U2") (pin "9") (pinfunction "IN4N_9") (pintype "unspecified"))
    )
    (net (code "36") (name "IN4P") (class "Default")
      (node (ref "C33") (pin "1") (pinfunction "1_1") (pintype "input"))
      (node (ref "R23") (pin "2") (pinfunction "2_2") (pintype "input"))
      (node (ref "U2") (pin "10") (pinfunction "IN4P_10") (pintype "unspecified"))
    )
    (net (code "37") (name "IN5N") (class "Default")
      (node (ref "C36") (pin "2") (pinfunction "2_2") (pintype "input"))
      (node (ref "R26") (pin "2") (pinfunction "2_2") (pintype "input"))
      (node (ref "U2") (pin "7") (pinfunction "IN5N_7") (pintype "unspecified"))
    )
    (net (code "38") (name "IN5P") (class "Default")
      (node (ref "C37") (pin "1") (pinfunction "1_1") (pintype "input"))
      (node (ref "R27") (pin "2") (pinfunction "2_2") (pintype "input"))
      (node (ref "U2") (pin "8") (pinfunction "IN5P_8") (pintype "unspecified"))
    )
    (net (code "39") (name "IN6N") (class "Default")
      (node (ref "C38") (pin "2") (pinfunction "2_2") (pintype "input"))
      (node (ref "R28") (pin "2") (pinfunction "2_2") (pintype "input"))
      (node (ref "U2") (pin "5") (pinfunction "IN6N_5") (pintype "unspecified"))
    )
    (net (code "40") (name "IN6P") (class "Default")
      (node (ref "C39") (pin "1") (pinfunction "1_1") (pintype "input"))
      (node (ref "R29") (pin "2") (pinfunction "2_2") (pintype "input"))
      (node (ref "U2") (pin "6") (pinfunction "IN6P_6") (pintype "unspecified"))
    )
    (net (code "41") (name "IN7N") (class "Default")
      (node (ref "C40") (pin "2") (pinfunction "2_2") (pintype "input"))
      (node (ref "R30") (pin "2") (pinfunction "2_2") (pintype "input"))
      (node (ref "U2") (pin "3") (pinfunction "IN7N_3") (pintype "unspecified"))
    )
    (net (code "42") (name "IN7P") (class "Default")
      (node (ref "C41") (pin "1") (pinfunction "1_1") (pintype "input"))
      (node (ref "R31") (pin "2") (pinfunction "2_2") (pintype "input"))
      (node (ref "U2") (pin "4") (pinfunction "IN7P_4") (pintype "unspecified"))
    )
    (net (code "43") (name "IN8N") (class "Default")
      (node (ref "C34") (pin "2") (pinfunction "2_2") (pintype "input"))
      (node (ref "R24") (pin "2") (pinfunction "2_2") (pintype "input"))
      (node (ref "U2") (pin "1") (pinfunction "IN8N_1") (pintype "unspecified"))
    )
    (net (code "44") (name "IN8P") (class "Default")
      (node (ref "C35") (pin "1") (pinfunction "1_1") (pintype "input"))
      (node (ref "R25") (pin "2") (pinfunction "2_2") (pintype "input"))
      (node (ref "U2") (pin "2") (pinfunction "IN8P_2") (pintype "unspecified"))
    )
    (net (code "45") (name "IO1") (class "Default")
      (node (ref "H2") (pin "3") (pinfunction "3_3") (pintype "unspecified"))
      (node (ref "U4") (pin "1") (pinfunction "PE2_1") (pintype "unspecified"))
    )
    (net (code "46") (name "IO2") (class "Default")
      (node (ref "H2") (pin "2") (pinfunction "2_2") (pintype "unspecified"))
      (node (ref "U4") (pin "2") (pinfunction "PE3_2") (pintype "unspecified"))
    )
    (net (code "47") (name "IO3") (class "Default")
      (node (ref "H2") (pin "1") (pinfunction "1_1") (pintype "unspecified"))
      (node (ref "U4") (pin "3") (pinfunction "PE4_3") (pintype "unspecified"))
    )
    (net (code "48") (name "JTCK{slash}SWCLK") (class "Default")
      (node (ref "U4") (pin "76") (pinfunction "PA14_76") (pintype "unspecified"))
      (node (ref "U9") (pin "2") (pinfunction "2_2") (pintype "unspecified"))
    )
    (net (code "49") (name "JTMS{slash}SWDIO") (class "Default")
      (node (ref "U4") (pin "72") (pinfunction "PA13_72") (pintype "unspecified"))
      (node (ref "U9") (pin "3") (pinfunction "3_3") (pintype "unspecified"))
    )
    (net (code "50") (name "MISO") (class "Default")
      (node (ref "H4") (pin "6") (pinfunction "6_6") (pintype "unspecified"))
      (node (ref "U2") (pin "43") (pinfunction "DOUT_43") (pintype "unspecified"))
      (node (ref "U4") (pin "90") (pinfunction "PB4_90") (pintype "unspecified"))
    )
    (net (code "51") (name "MOSI") (class "Default")
      (node (ref "H4") (pin "5") (pinfunction "5_5") (pintype "unspecified"))
      (node (ref "U2") (pin "34") (pinfunction "DIN_34") (pintype "unspecified"))
      (node (ref "U4") (pin "91") (pinfunction "PB5_91") (pintype "unspecified"))
    )
    (net (code "52") (name "NRST") (class "Default")
      (node (ref "C19") (pin "2") (pinfunction "2_2") (pintype "unspecified"))
      (node (ref "SW1") (pin "1") (pinfunction "1_1") (pintype "unspecified"))
      (node (ref "U4") (pin "14") (pinfunction "NRST_14") (pintype "unspecified"))
      (node (ref "U9") (pin "1") (pinfunction "1_1") (pintype "unspecified"))
    )
    (net (code "53") (name "Net-(LED1-+)") (class "Default")
      (node (ref "LED1") (pin "2") (pinfunction "+_2") (pintype "input"))
      (node (ref "U4") (pin "38") (pinfunction "PE7_38") (pintype "unspecified"))
    )
    (net (code "54") (name "Net-(LED1--)") (class "Default")
      (node (ref "LED1") (pin "1") (pinfunction "-_1") (pintype "input"))
      (node (ref "R37") (pin "2") (pinfunction "2_2") (pintype "unspecified"))
    )
    (net (code "55") (name "Net-(LED2-+)") (class "Default")
      (node (ref "LED2") (pin "2") (pinfunction "+_2") (pintype "input"))
      (node (ref "U4") (pin "39") (pinfunction "PE8_39") (pintype "unspecified"))
    )
    (net (code "56") (name "Net-(LED2--)") (class "Default")
      (node (ref "LED2") (pin "1") (pinfunction "-_1") (pintype "input"))
      (node (ref "R38") (pin "2") (pinfunction "2_2") (pintype "unspecified"))
    )
    (net (code "57") (name "Net-(LED3-+)") (class "Default")
      (node (ref "LED3") (pin "2") (pinfunction "+_2") (pintype "input"))
      (node (ref "U4") (pin "41") (pinfunction "PE10_41") (pintype "unspecified"))
    )
    (net (code "58") (name "Net-(LED3--)") (class "Default")
      (node (ref "LED3") (pin "1") (pinfunction "-_1") (pintype "input"))
      (node (ref "R39") (pin "2") (pinfunction "2_2") (pintype "unspecified"))
    )
    (net (code "59") (name "Net-(LED4-A)") (class "Default")
      (node (ref "LED4") (pin "1") (pinfunction "A_1") (pintype "unspecified"))
      (node (ref "R41") (pin "1") (pinfunction "1_1") (pintype "unspecified"))
    )
    (net (code "60") (name "Net-(LED5-K)") (class "Default")
      (node (ref "LED5") (pin "1") (pinfunction "K_1") (pintype "unspecified"))
      (node (ref "R42") (pin "1") (pinfunction "1_1") (pintype "unspecified"))
    )
    (net (code "61") (name "Net-(LED6-K)") (class "Default")
      (node (ref "LED6") (pin "1") (pinfunction "K_1") (pintype "unspecified"))
      (node (ref "R43") (pin "2") (pinfunction "2_2") (pintype "unspecified"))
    )
    (net (code "62") (name "Net-(LED7-K)") (class "Default")
      (node (ref "LED7") (pin "2") (pinfunction "K_2") (pintype "unspecified"))
      (node (ref "R44") (pin "1") (pinfunction "1_1") (pintype "unspecified"))
    )
    (net (code "63") (name "Net-(LED8-A)") (class "Default")
      (node (ref "LED8") (pin "1") (pinfunction "A_1") (pintype "unspecified"))
      (node (ref "R40") (pin "2") (pinfunction "2_2") (pintype "unspecified"))
    )
    (net (code "64") (name "Net-(U2-GPIO1)") (class "Default")
      (node (ref "R40") (pin "1") (pinfunction "1_1") (pintype "unspecified"))
      (node (ref "U2") (pin "42") (pinfunction "GPIO1_42") (pintype "unspecified"))
    )
    (net (code "65") (name "Net-(U2-VCAP1)") (class "Default")
      (node (ref "C88") (pin "1") (pinfunction "1_1") (pintype "input"))
      (node (ref "U2") (pin "28") (pinfunction "VCAP1_28") (pintype "unspecified"))
    )
    (net (code "66") (name "Net-(U2-VCAP2)") (class "Default")
      (node (ref "C12") (pin "2") (pinfunction "2_2") (pintype "input"))
      (node (ref "U2") (pin "30") (pinfunction "VCAP2_30") (pintype "unspecified"))
    )
    (net (code "67") (name "Net-(U2-VCAP3)") (class "Default")
      (node (ref "C14") (pin "2") (pinfunction "2_2") (pintype "unspecified"))
      (node (ref "C15") (pin "1") (pinfunction "1_1") (pintype "input"))
      (node (ref "U2") (pin "55") (pinfunction "VCAP3_55") (pintype "unspecified"))
    )
    (net (code "68") (name "Net-(U2-VCAP4)") (class "Default")
      (node (ref "C11") (pin "1") (pinfunction "1_1") (pintype "input"))
      (node (ref "U2") (pin "26") (pinfunction "VCAP4_26") (pintype "unspecified"))
    )
    (net (code "69") (name "Net-(U4-BOOT0)") (class "Default")
      (node (ref "R35") (pin "1") (pinfunction "1_1") (pintype "unspecified"))
      (node (ref "U4") (pin "94") (pinfunction "BOOT0_94") (pintype "unspecified"))
    )
    (net (code "70") (name "Net-(U4-PB2)") (class "Default")
      (node (ref "R36") (pin "1") (pinfunction "1_1") (pintype "unspecified"))
      (node (ref "U4") (pin "37") (pinfunction "PB2_37") (pintype "unspecified"))
    )
    (net (code "71") (name "Net-(U4-PH0)") (class "Default")
      (node (ref "C59") (pin "2") (pinfunction "2_2") (pintype "unspecified"))
      (node (ref "U4") (pin "12") (pinfunction "PH0_12") (pintype "unspecified"))
      (node (ref "X2") (pin "3") (pinfunction "OSC2_3") (pintype "unspecified"))
    )
    (net (code "72") (name "Net-(U4-PH1)") (class "Default")
      (node (ref "C60") (pin "2") (pinfunction "2_2") (pintype "unspecified"))
      (node (ref "U4") (pin "13") (pinfunction "PH1_13") (pintype "unspecified"))
      (node (ref "X2") (pin "1") (pinfunction "OSC1_1") (pintype "unspecified"))
    )
    (net (code "73") (name "Net-(U4-VCAP_1)") (class "Default")
      (node (ref "C57") (pin "1") (pinfunction "1_1") (pintype "input"))
      (node (ref "U4") (pin "49") (pinfunction "VCAP_1_49") (pintype "unspecified"))
    )
    (net (code "74") (name "Net-(U4-VCAP_2)") (class "Default")
      (node (ref "C58") (pin "1") (pinfunction "1_1") (pintype "input"))
      (node (ref "U4") (pin "73") (pinfunction "VCAP_2_73") (pintype "unspecified"))
    )
    (net (code "75") (name "Net-(U5-CFLY+)") (class "Default")
      (node (ref "C74") (pin "2") (pinfunction "2_2") (pintype "input"))
      (node (ref "U5") (pin "5") (pinfunction "CFLY+_5") (pintype "input"))
    )
    (net (code "76") (name "Net-(U5-CFLY-)") (class "Default")
      (node (ref "C74") (pin "1") (pinfunction "1_1") (pintype "input"))
      (node (ref "U5") (pin "3") (pinfunction "CFLY-_3") (pintype "input"))
    )
    (net (code "77") (name "Net-(U6-NR{slash}FB)") (class "Default")
      (node (ref "C82") (pin "2") (pinfunction "2_2") (pintype "input"))
      (node (ref "U6") (pin "4") (pinfunction "NR/FB_4") (pintype "unspecified"))
    )
    (net (code "78") (name "Net-(U7-NR{slash}FB)") (class "Default")
      (node (ref "C61") (pin "2") (pinfunction "2_2") (pintype "input"))
      (node (ref "U7") (pin "4") (pinfunction "NR/FB_4") (pintype "input"))
    )
    (net (code "79") (name "Net-(U8-NR{slash}FB)") (class "Default")
      (node (ref "C67") (pin "2") (pinfunction "2_2") (pintype "input"))
      (node (ref "U8") (pin "4") (pinfunction "NR/FB_4") (pintype "input"))
    )
    (net (code "80") (name "PWDN") (class "Default")
      (node (ref "H4") (pin "1") (pinfunction "1_1") (pintype "unspecified"))
      (node (ref "R9") (pin "1") (pinfunction "1_1") (pintype "unspecified"))
      (node (ref "U2") (pin "35") (pinfunction "PWDN#_35") (pintype "unspecified"))
      (node (ref "U4") (pin "95") (pinfunction "PB8_95") (pintype "unspecified"))
    )
    (net (code "81") (name "RESET") (class "Default")
      (node (ref "H4") (pin "2") (pinfunction "2_2") (pintype "unspecified"))
      (node (ref "R8") (pin "1") (pinfunction "1_1") (pintype "unspecified"))
      (node (ref "U2") (pin "36") (pinfunction "RESET#_36") (pintype "unspecified"))
      (node (ref "U4") (pin "93") (pinfunction "PB7_93") (pintype "unspecified"))
    )
    (net (code "82") (name "SCLK") (class "Default")
      (node (ref "H4") (pin "8") (pinfunction "8_8") (pintype "unspecified"))
      (node (ref "U2") (pin "40") (pinfunction "SCLK_40") (pintype "unspecified"))
      (node (ref "U4") (pin "89") (pinfunction "PB3_89") (pintype "unspecified"))
    )
    (net (code "83") (name "SRB1") (class "Default")
      (node (ref "C42") (pin "2") (pinfunction "2_2") (pintype "input"))
      (node (ref "R32") (pin "2") (pinfunction "2_2") (pintype "input"))
      (node (ref "U2") (pin "17") (pinfunction "SRB1_17") (pintype "unspecified"))
    )
    (net (code "84") (name "SRB2") (class "Default")
      (node (ref "C43") (pin "1") (pinfunction "1_1") (pintype "input"))
      (node (ref "R33") (pin "2") (pinfunction "2_2") (pintype "input"))
      (node (ref "U2") (pin "18") (pinfunction "SRB2_18") (pintype "unspecified"))
    )
    (net (code "85") (name "START") (class "Default")
      (node (ref "H4") (pin "4") (pinfunction "4_4") (pintype "unspecified"))
      (node (ref "U2") (pin "38") (pinfunction "START_38") (pintype "unspecified"))
      (node (ref "U4") (pin "92") (pinfunction "PB6_92") (pintype "unspecified"))
    )
    (net (code "86") (name "USART1{slash}RX") (class "Default")
      (node (ref "U4") (pin "69") (pinfunction "PA10_69") (pintype "unspecified"))
      (node (ref "U9") (pin "6") (pinfunction "6_6") (pintype "unspecified"))
    )
    (net (code "87") (name "USART1{slash}TX") (class "Default")
      (node (ref "U4") (pin "68") (pinfunction "PA9_68") (pintype "unspecified"))
      (node (ref "U9") (pin "5") (pinfunction "5_5") (pintype "unspecified"))
    )
    (net (code "88") (name "USART2{slash}RX") (class "Default")
      (node (ref "H2") (pin "4") (pinfunction "4_4") (pintype "unspecified"))
      (node (ref "U4") (pin "26") (pinfunction "PA3_26") (pintype "unspecified"))
    )
    (net (code "89") (name "USART2{slash}TX") (class "Default")
      (node (ref "H2") (pin "5") (pinfunction "5_5") (pintype "unspecified"))
      (node (ref "U4") (pin "25") (pinfunction "PA2_25") (pintype "unspecified"))
    )
    (net (code "90") (name "USART3{slash}RX") (class "Default")
      (node (ref "U10") (pin "4") (pinfunction "4_4") (pintype "unspecified"))
      (node (ref "U4") (pin "48") (pinfunction "PB11_48") (pintype "unspecified"))
    )
    (net (code "91") (name "USART3{slash}TX") (class "Default")
      (node (ref "U10") (pin "3") (pinfunction "3_3") (pintype "unspecified"))
      (node (ref "U4") (pin "47") (pinfunction "PB10_47") (pintype "unspecified"))
    )
    (net (code "92") (name "VDD") (class "Default")
      (node (ref "C64") (pin "1") (pinfunction "1_1") (pintype "unspecified"))
      (node (ref "C65") (pin "1") (pinfunction "1_1") (pintype "unspecified"))
      (node (ref "C66") (pin "2") (pinfunction "2_2") (pintype "input"))
      (node (ref "C71") (pin "1") (pinfunction "1_1") (pintype "unspecified"))
      (node (ref "C72") (pin "1") (pinfunction "1_1") (pintype "unspecified"))
      (node (ref "C73") (pin "2") (pinfunction "2_2") (pintype "input"))
      (node (ref "C77") (pin "2") (pinfunction "2_2") (pintype "input"))
      (node (ref "C78") (pin "1") (pinfunction "1_1") (pintype "unspecified"))
      (node (ref "H5") (pin "10") (pinfunction "10_10") (pintype "unspecified"))
      (node (ref "H5") (pin "9") (pinfunction "9_9") (pintype "unspecified"))
      (node (ref "U5") (pin "2") (pinfunction "IN_2") (pintype "input"))
      (node (ref "U7") (pin "1") (pinfunction "IN_1") (pintype "input"))
      (node (ref "U7") (pin "3") (pinfunction "EN_3") (pintype "input"))
      (node (ref "U8") (pin "1") (pinfunction "IN_1") (pintype "input"))
      (node (ref "U8") (pin "3") (pinfunction "EN_3") (pintype "input"))
      (node (ref "USB2") (pin "A9") (pinfunction "VBUS_A9") (pintype "unspecified"))
      (node (ref "USB2") (pin "B9") (pinfunction "VBUS_B9") (pintype "unspecified"))
    )
    (net (code "93") (name "VREFP") (class "Default")
      (node (ref "C105") (pin "2") (pinfunction "2_2") (pintype "unspecified"))
      (node (ref "C87") (pin "1") (pinfunction "1_1") (pintype "input"))
      (node (ref "H2") (pin "10") (pinfunction "10_10") (pintype "unspecified"))
      (node (ref "H2") (pin "9") (pinfunction "9_9") (pintype "unspecified"))
      (node (ref "U2") (pin "24") (pinfunction "VREFP_24") (pintype "unspecified"))
    )
    (net (code "94") (name "VSS") (class "Default")
      (node (ref "C75") (pin "2") (pinfunction "2_2") (pintype "input"))
      (node (ref "C76") (pin "1") (pinfunction "1_1") (pintype "unspecified"))
      (node (ref "C83") (pin "2") (pinfunction "2_2") (pintype "unspecified"))
      (node (ref "C84") (pin "1") (pinfunction "1_1") (pintype "unspecified"))
      (node (ref "H5") (pin "7") (pinfunction "7_7") (pintype "unspecified"))
      (node (ref "H5") (pin "8") (pinfunction "8_8") (pintype "unspecified"))
      (node (ref "R44") (pin "2") (pinfunction "2_2") (pintype "unspecified"))
      (node (ref "U5") (pin "1") (pinfunction "OUT_1") (pintype "input"))
      (node (ref "U6") (pin "2") (pinfunction "IN_2") (pintype "unspecified"))
      (node (ref "U6") (pin "3") (pinfunction "EN_3") (pintype "unspecified"))
    )
    (net (code "95") (name "unconnected-(SCREW1-Pad1)") (class "Default")
      (node (ref "SCREW1") (pin "1") (pinfunction "1_1") (pintype "input+no_connect"))
    )
    (net (code "96") (name "unconnected-(SCREW2-Pad1)") (class "Default")
      (node (ref "SCREW2") (pin "1") (pinfunction "1_1") (pintype "input+no_connect"))
    )
    (net (code "97") (name "unconnected-(SCREW3-Pad1)") (class "Default")
      (node (ref "SCREW3") (pin "1") (pinfunction "1_1") (pintype "input+no_connect"))
    )
    (net (code "98") (name "unconnected-(SCREW4-Pad1)") (class "Default")
      (node (ref "SCREW4") (pin "1") (pinfunction "1_1") (pintype "input+no_connect"))
    )
    (net (code "99") (name "unconnected-(U2-GPIO2-Pad44)") (class "Default")
      (node (ref "U2") (pin "44") (pinfunction "GPIO2_44") (pintype "unspecified+no_connect"))
    )
    (net (code "100") (name "unconnected-(U2-NC-Pad27)") (class "Default")
      (node (ref "U2") (pin "27") (pinfunction "NC_27") (pintype "unspecified+no_connect"))
    )
    (net (code "101") (name "unconnected-(U2-NC-Pad29)") (class "Default")
      (node (ref "U2") (pin "29") (pinfunction "NC_29") (pintype "unspecified+no_connect"))
    )
    (net (code "102") (name "unconnected-(U2-RESERVED-Pad64)") (class "Default")
      (node (ref "U2") (pin "64") (pinfunction "RESERVED_64") (pintype "unspecified+no_connect"))
    )
    (net (code "103") (name "unconnected-(U4-PA0-Pad23)") (class "Default")
      (node (ref "U4") (pin "23") (pinfunction "PA0_23") (pintype "unspecified+no_connect"))
    )
    (net (code "104") (name "unconnected-(U4-PA1-Pad24)") (class "Default")
      (node (ref "U4") (pin "24") (pinfunction "PA1_24") (pintype "unspecified+no_connect"))
    )
    (net (code "105") (name "unconnected-(U4-PA4-Pad29)") (class "Default")
      (node (ref "U4") (pin "29") (pinfunction "PA4_29") (pintype "unspecified+no_connect"))
    )
    (net (code "106") (name "unconnected-(U4-PA5-Pad30)") (class "Default")
      (node (ref "U4") (pin "30") (pinfunction "PA5_30") (pintype "unspecified+no_connect"))
    )
    (net (code "107") (name "unconnected-(U4-PA6-Pad31)") (class "Default")
      (node (ref "U4") (pin "31") (pinfunction "PA6_31") (pintype "unspecified+no_connect"))
    )
    (net (code "108") (name "unconnected-(U4-PA7-Pad32)") (class "Default")
      (node (ref "U4") (pin "32") (pinfunction "PA7_32") (pintype "unspecified+no_connect"))
    )
    (net (code "109") (name "unconnected-(U4-PA8-Pad67)") (class "Default")
      (node (ref "U4") (pin "67") (pinfunction "PA8_67") (pintype "unspecified+no_connect"))
    )
    (net (code "110") (name "unconnected-(U4-PA11-Pad70)") (class "Default")
      (node (ref "U4") (pin "70") (pinfunction "PA11_70") (pintype "unspecified+no_connect"))
    )
    (net (code "111") (name "unconnected-(U4-PA12-Pad71)") (class "Default")
      (node (ref "U4") (pin "71") (pinfunction "PA12_71") (pintype "unspecified+no_connect"))
    )
    (net (code "112") (name "unconnected-(U4-PA15-Pad77)") (class "Default")
      (node (ref "U4") (pin "77") (pinfunction "PA15_77") (pintype "unspecified+no_connect"))
    )
    (net (code "113") (name "unconnected-(U4-PB0-Pad35)") (class "Default")
      (node (ref "U4") (pin "35") (pinfunction "PB0_35") (pintype "unspecified+no_connect"))
    )
    (net (code "114") (name "unconnected-(U4-PB1-Pad36)") (class "Default")
      (node (ref "U4") (pin "36") (pinfunction "PB1_36") (pintype "unspecified+no_connect"))
    )
    (net (code "115") (name "unconnected-(U4-PB9-Pad96)") (class "Default")
      (node (ref "U4") (pin "96") (pinfunction "PB9_96") (pintype "unspecified+no_connect"))
    )
    (net (code "116") (name "unconnected-(U4-PB12-Pad51)") (class "Default")
      (node (ref "U4") (pin "51") (pinfunction "PB12_51") (pintype "unspecified+no_connect"))
    )
    (net (code "117") (name "unconnected-(U4-PB13-Pad52)") (class "Default")
      (node (ref "U4") (pin "52") (pinfunction "PB13_52") (pintype "unspecified+no_connect"))
    )
    (net (code "118") (name "unconnected-(U4-PB14-Pad53)") (class "Default")
      (node (ref "U4") (pin "53") (pinfunction "PB14_53") (pintype "unspecified+no_connect"))
    )
    (net (code "119") (name "unconnected-(U4-PB15-Pad54)") (class "Default")
      (node (ref "U4") (pin "54") (pinfunction "PB15_54") (pintype "unspecified+no_connect"))
    )
    (net (code "120") (name "unconnected-(U4-PC0-Pad15)") (class "Default")
      (node (ref "U4") (pin "15") (pinfunction "PC0_15") (pintype "unspecified+no_connect"))
    )
    (net (code "121") (name "unconnected-(U4-PC1-Pad16)") (class "Default")
      (node (ref "U4") (pin "16") (pinfunction "PC1_16") (pintype "unspecified+no_connect"))
    )
    (net (code "122") (name "unconnected-(U4-PC2-Pad17)") (class "Default")
      (node (ref "U4") (pin "17") (pinfunction "PC2_17") (pintype "unspecified+no_connect"))
    )
    (net (code "123") (name "unconnected-(U4-PC3-Pad18)") (class "Default")
      (node (ref "U4") (pin "18") (pinfunction "PC3_18") (pintype "unspecified+no_connect"))
    )
    (net (code "124") (name "unconnected-(U4-PC4-Pad33)") (class "Default")
      (node (ref "U4") (pin "33") (pinfunction "PC4_33") (pintype "unspecified+no_connect"))
    )
    (net (code "125") (name "unconnected-(U4-PC5-Pad34)") (class "Default")
      (node (ref "U4") (pin "34") (pinfunction "PC5_34") (pintype "unspecified+no_connect"))
    )
    (net (code "126") (name "unconnected-(U4-PC6-Pad63)") (class "Default")
      (node (ref "U4") (pin "63") (pinfunction "PC6_63") (pintype "unspecified+no_connect"))
    )
    (net (code "127") (name "unconnected-(U4-PC7-Pad64)") (class "Default")
      (node (ref "U4") (pin "64") (pinfunction "PC7_64") (pintype "unspecified+no_connect"))
    )
    (net (code "128") (name "unconnected-(U4-PC8-Pad65)") (class "Default")
      (node (ref "U4") (pin "65") (pinfunction "PC8_65") (pintype "unspecified+no_connect"))
    )
    (net (code "129") (name "unconnected-(U4-PC9-Pad66)") (class "Default")
      (node (ref "U4") (pin "66") (pinfunction "PC9_66") (pintype "unspecified+no_connect"))
    )
    (net (code "130") (name "unconnected-(U4-PC10-Pad78)") (class "Default")
      (node (ref "U4") (pin "78") (pinfunction "PC10_78") (pintype "unspecified+no_connect"))
    )
    (net (code "131") (name "unconnected-(U4-PC11-Pad79)") (class "Default")
      (node (ref "U4") (pin "79") (pinfunction "PC11_79") (pintype "unspecified+no_connect"))
    )
    (net (code "132") (name "unconnected-(U4-PC12-Pad80)") (class "Default")
      (node (ref "U4") (pin "80") (pinfunction "PC12_80") (pintype "unspecified+no_connect"))
    )
    (net (code "133") (name "unconnected-(U4-PC13-Pad7)") (class "Default")
      (node (ref "U4") (pin "7") (pinfunction "PC13_7") (pintype "unspecified+no_connect"))
    )
    (net (code "134") (name "unconnected-(U4-PC14-Pad8)") (class "Default")
      (node (ref "U4") (pin "8") (pinfunction "PC14_8") (pintype "unspecified+no_connect"))
    )
    (net (code "135") (name "unconnected-(U4-PC15-Pad9)") (class "Default")
      (node (ref "U4") (pin "9") (pinfunction "PC15_9") (pintype "unspecified+no_connect"))
    )
    (net (code "136") (name "unconnected-(U4-PD0-Pad81)") (class "Default")
      (node (ref "U4") (pin "81") (pinfunction "PD0_81") (pintype "unspecified+no_connect"))
    )
    (net (code "137") (name "unconnected-(U4-PD1-Pad82)") (class "Default")
      (node (ref "U4") (pin "82") (pinfunction "PD1_82") (pintype "unspecified+no_connect"))
    )
    (net (code "138") (name "unconnected-(U4-PD2-Pad83)") (class "Default")
      (node (ref "U4") (pin "83") (pinfunction "PD2_83") (pintype "unspecified+no_connect"))
    )
    (net (code "139") (name "unconnected-(U4-PD3-Pad84)") (class "Default")
      (node (ref "U4") (pin "84") (pinfunction "PD3_84") (pintype "unspecified+no_connect"))
    )
    (net (code "140") (name "unconnected-(U4-PD4-Pad85)") (class "Default")
      (node (ref "U4") (pin "85") (pinfunction "PD4_85") (pintype "unspecified+no_connect"))
    )
    (net (code "141") (name "unconnected-(U4-PD5-Pad86)") (class "Default")
      (node (ref "U4") (pin "86") (pinfunction "PD5_86") (pintype "unspecified+no_connect"))
    )
    (net (code "142") (name "unconnected-(U4-PD8-Pad55)") (class "Default")
      (node (ref "U4") (pin "55") (pinfunction "PD8_55") (pintype "unspecified+no_connect"))
    )
    (net (code "143") (name "unconnected-(U4-PD9-Pad56)") (class "Default")
      (node (ref "U4") (pin "56") (pinfunction "PD9_56") (pintype "unspecified+no_connect"))
    )
    (net (code "144") (name "unconnected-(U4-PD10-Pad57)") (class "Default")
      (node (ref "U4") (pin "57") (pinfunction "PD10_57") (pintype "unspecified+no_connect"))
    )
    (net (code "145") (name "unconnected-(U4-PD11-Pad58)") (class "Default")
      (node (ref "U4") (pin "58") (pinfunction "PD11_58") (pintype "unspecified+no_connect"))
    )
    (net (code "146") (name "unconnected-(U4-PD12-Pad59)") (class "Default")
      (node (ref "U4") (pin "59") (pinfunction "PD12_59") (pintype "unspecified+no_connect"))
    )
    (net (code "147") (name "unconnected-(U4-PD13-Pad60)") (class "Default")
      (node (ref "U4") (pin "60") (pinfunction "PD13_60") (pintype "unspecified+no_connect"))
    )
    (net (code "148") (name "unconnected-(U4-PD14-Pad61)") (class "Default")
      (node (ref "U4") (pin "61") (pinfunction "PD14_61") (pintype "unspecified+no_connect"))
    )
    (net (code "149") (name "unconnected-(U4-PD15-Pad62)") (class "Default")
      (node (ref "U4") (pin "62") (pinfunction "PD15_62") (pintype "unspecified+no_connect"))
    )
    (net (code "150") (name "unconnected-(U4-PE0-Pad97)") (class "Default")
      (node (ref "U4") (pin "97") (pinfunction "PE0_97") (pintype "unspecified+no_connect"))
    )
    (net (code "151") (name "unconnected-(U4-PE1-Pad98)") (class "Default")
      (node (ref "U4") (pin "98") (pinfunction "PE1_98") (pintype "unspecified+no_connect"))
    )
    (net (code "152") (name "unconnected-(U4-PE5-Pad4)") (class "Default")
      (node (ref "U4") (pin "4") (pinfunction "PE5_4") (pintype "unspecified+no_connect"))
    )
    (net (code "153") (name "unconnected-(U4-PE6-Pad5)") (class "Default")
      (node (ref "U4") (pin "5") (pinfunction "PE6_5") (pintype "unspecified+no_connect"))
    )
    (net (code "154") (name "unconnected-(U4-PE9-Pad40)") (class "Default")
      (node (ref "U4") (pin "40") (pinfunction "PE9_40") (pintype "unspecified+no_connect"))
    )
    (net (code "155") (name "unconnected-(U4-PE11-Pad42)") (class "Default")
      (node (ref "U4") (pin "42") (pinfunction "PE11_42") (pintype "unspecified+no_connect"))
    )
    (net (code "156") (name "unconnected-(U4-PE12-Pad43)") (class "Default")
      (node (ref "U4") (pin "43") (pinfunction "PE12_43") (pintype "unspecified+no_connect"))
    )
    (net (code "157") (name "unconnected-(U4-PE13-Pad44)") (class "Default")
      (node (ref "U4") (pin "44") (pinfunction "PE13_44") (pintype "unspecified+no_connect"))
    )
    (net (code "158") (name "unconnected-(U4-PE14-Pad45)") (class "Default")
      (node (ref "U4") (pin "45") (pinfunction "PE14_45") (pintype "unspecified+no_connect"))
    )
    (net (code "159") (name "unconnected-(U4-PE15-Pad46)") (class "Default")
      (node (ref "U4") (pin "46") (pinfunction "PE15_46") (pintype "unspecified+no_connect"))
    )
    (net (code "160") (name "unconnected-(U10-Pad2)") (class "Default")
      (node (ref "U10") (pin "2") (pinfunction "2_2") (pintype "unspecified+no_connect"))
    )
    (net (code "161") (name "unconnected-(U10-Pad7)") (class "Default")
      (node (ref "U10") (pin "7") (pinfunction "7_7") (pintype "unspecified+no_connect"))
    )
    (net (code "162") (name "unconnected-(USB2-CC1-PadA5)") (class "Default")
      (node (ref "USB2") (pin "A5") (pinfunction "CC1_A5") (pintype "unspecified+no_connect"))
    )
    (net (code "163") (name "unconnected-(USB2-CC2-PadB5)") (class "Default")
      (node (ref "USB2") (pin "B5") (pinfunction "CC2_B5") (pintype "unspecified+no_connect"))
    )
    (net (code "164") (name "unconnected-(USB2-EH-Pad7)") (class "Default")
      (node (ref "USB2") (pin "7") (pinfunction "EH_7") (pintype "unspecified+no_connect"))
    )
  )
)
